# e1-tracer.net
KiCad netlist of a schematic drawn in EAGLE
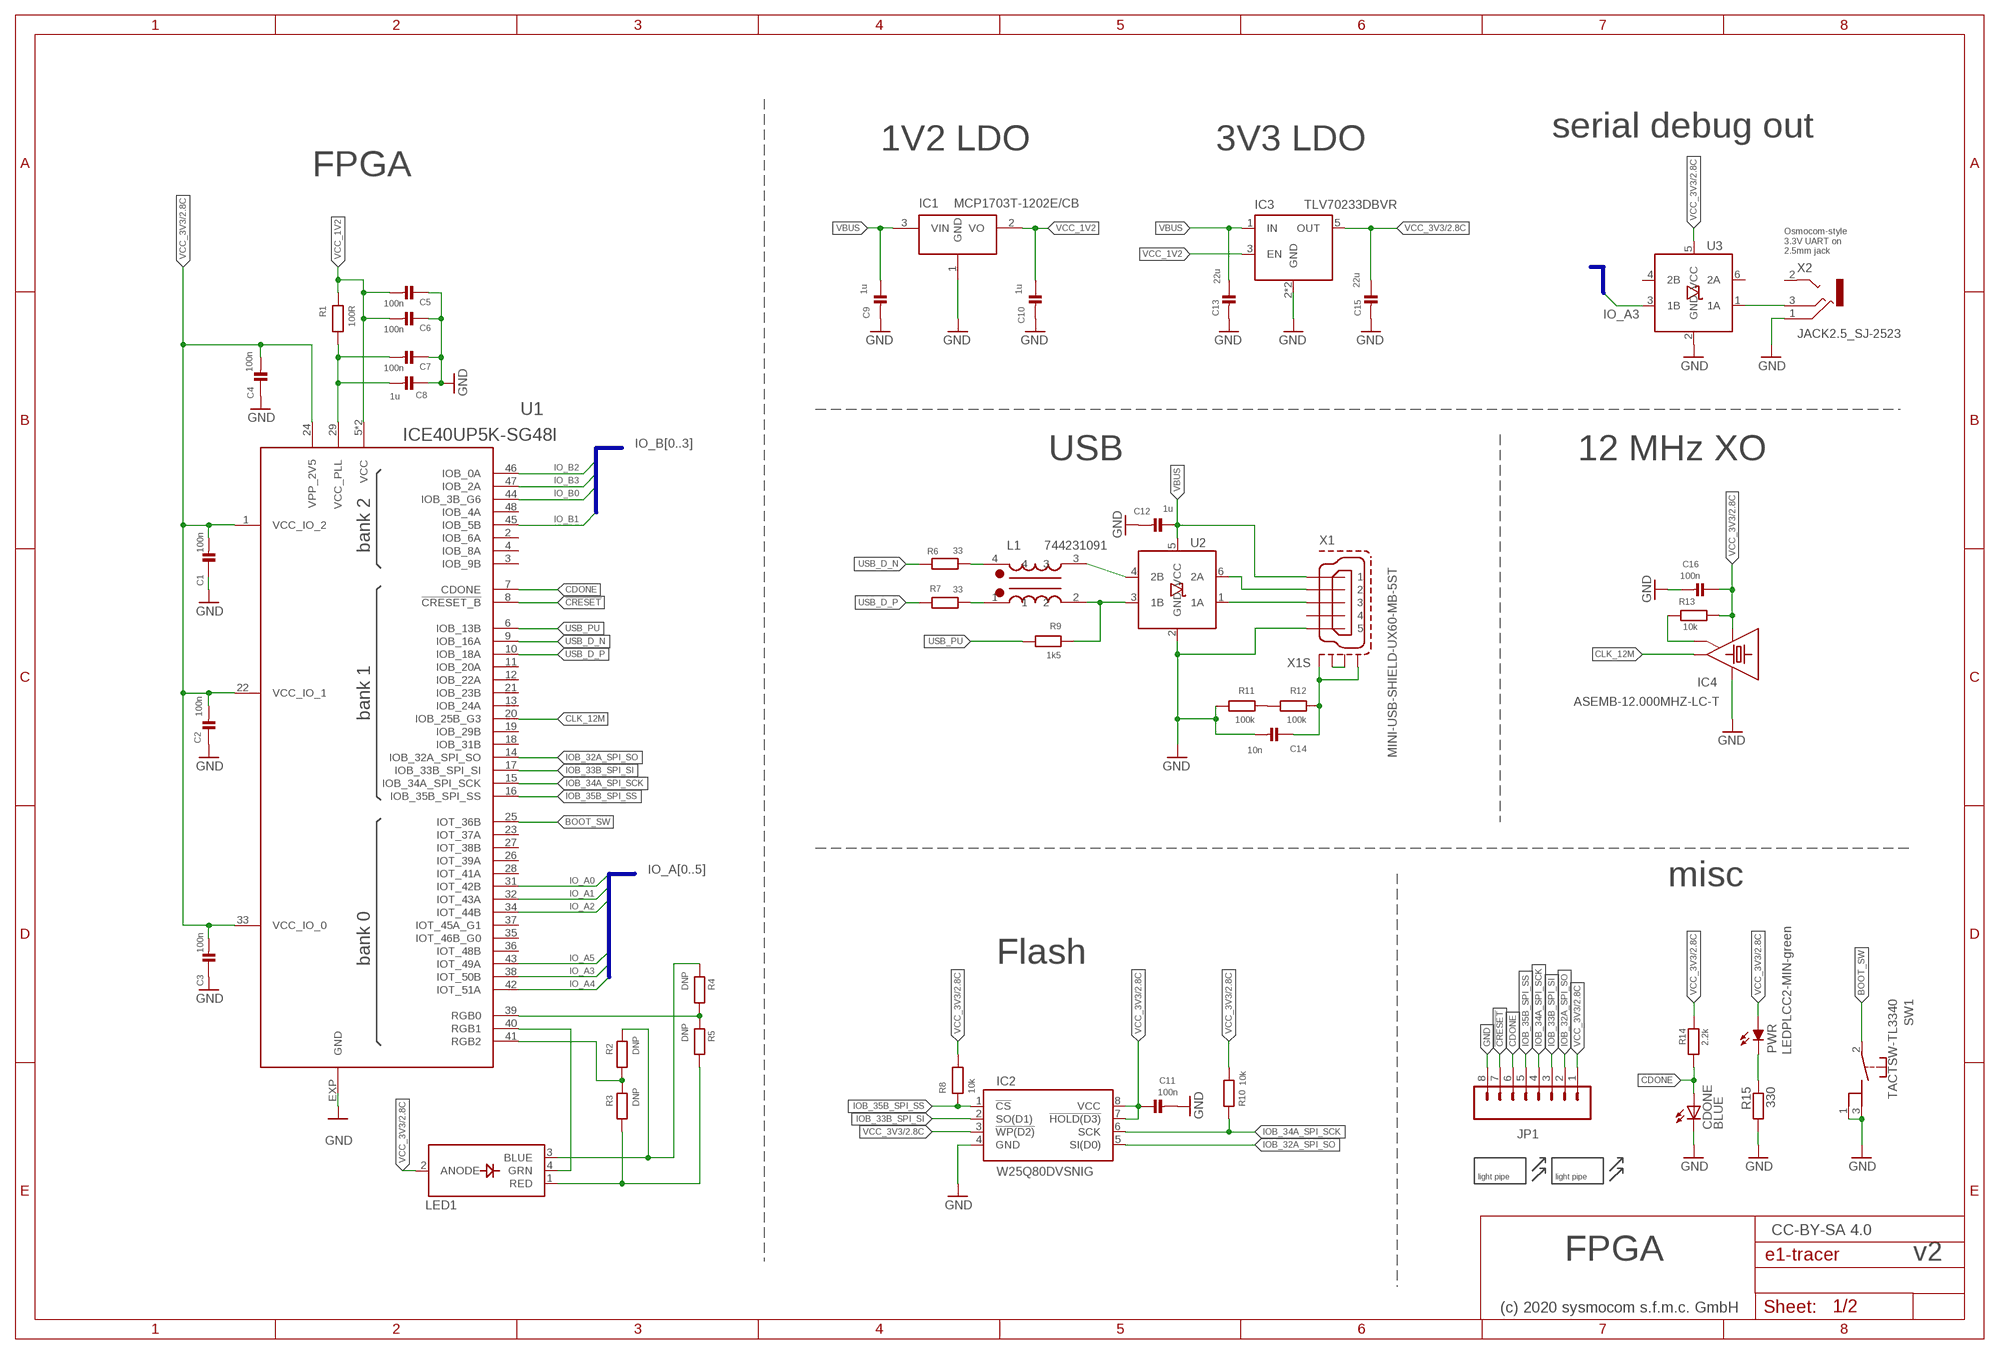
[diagram p0: schematic, sheet 1]
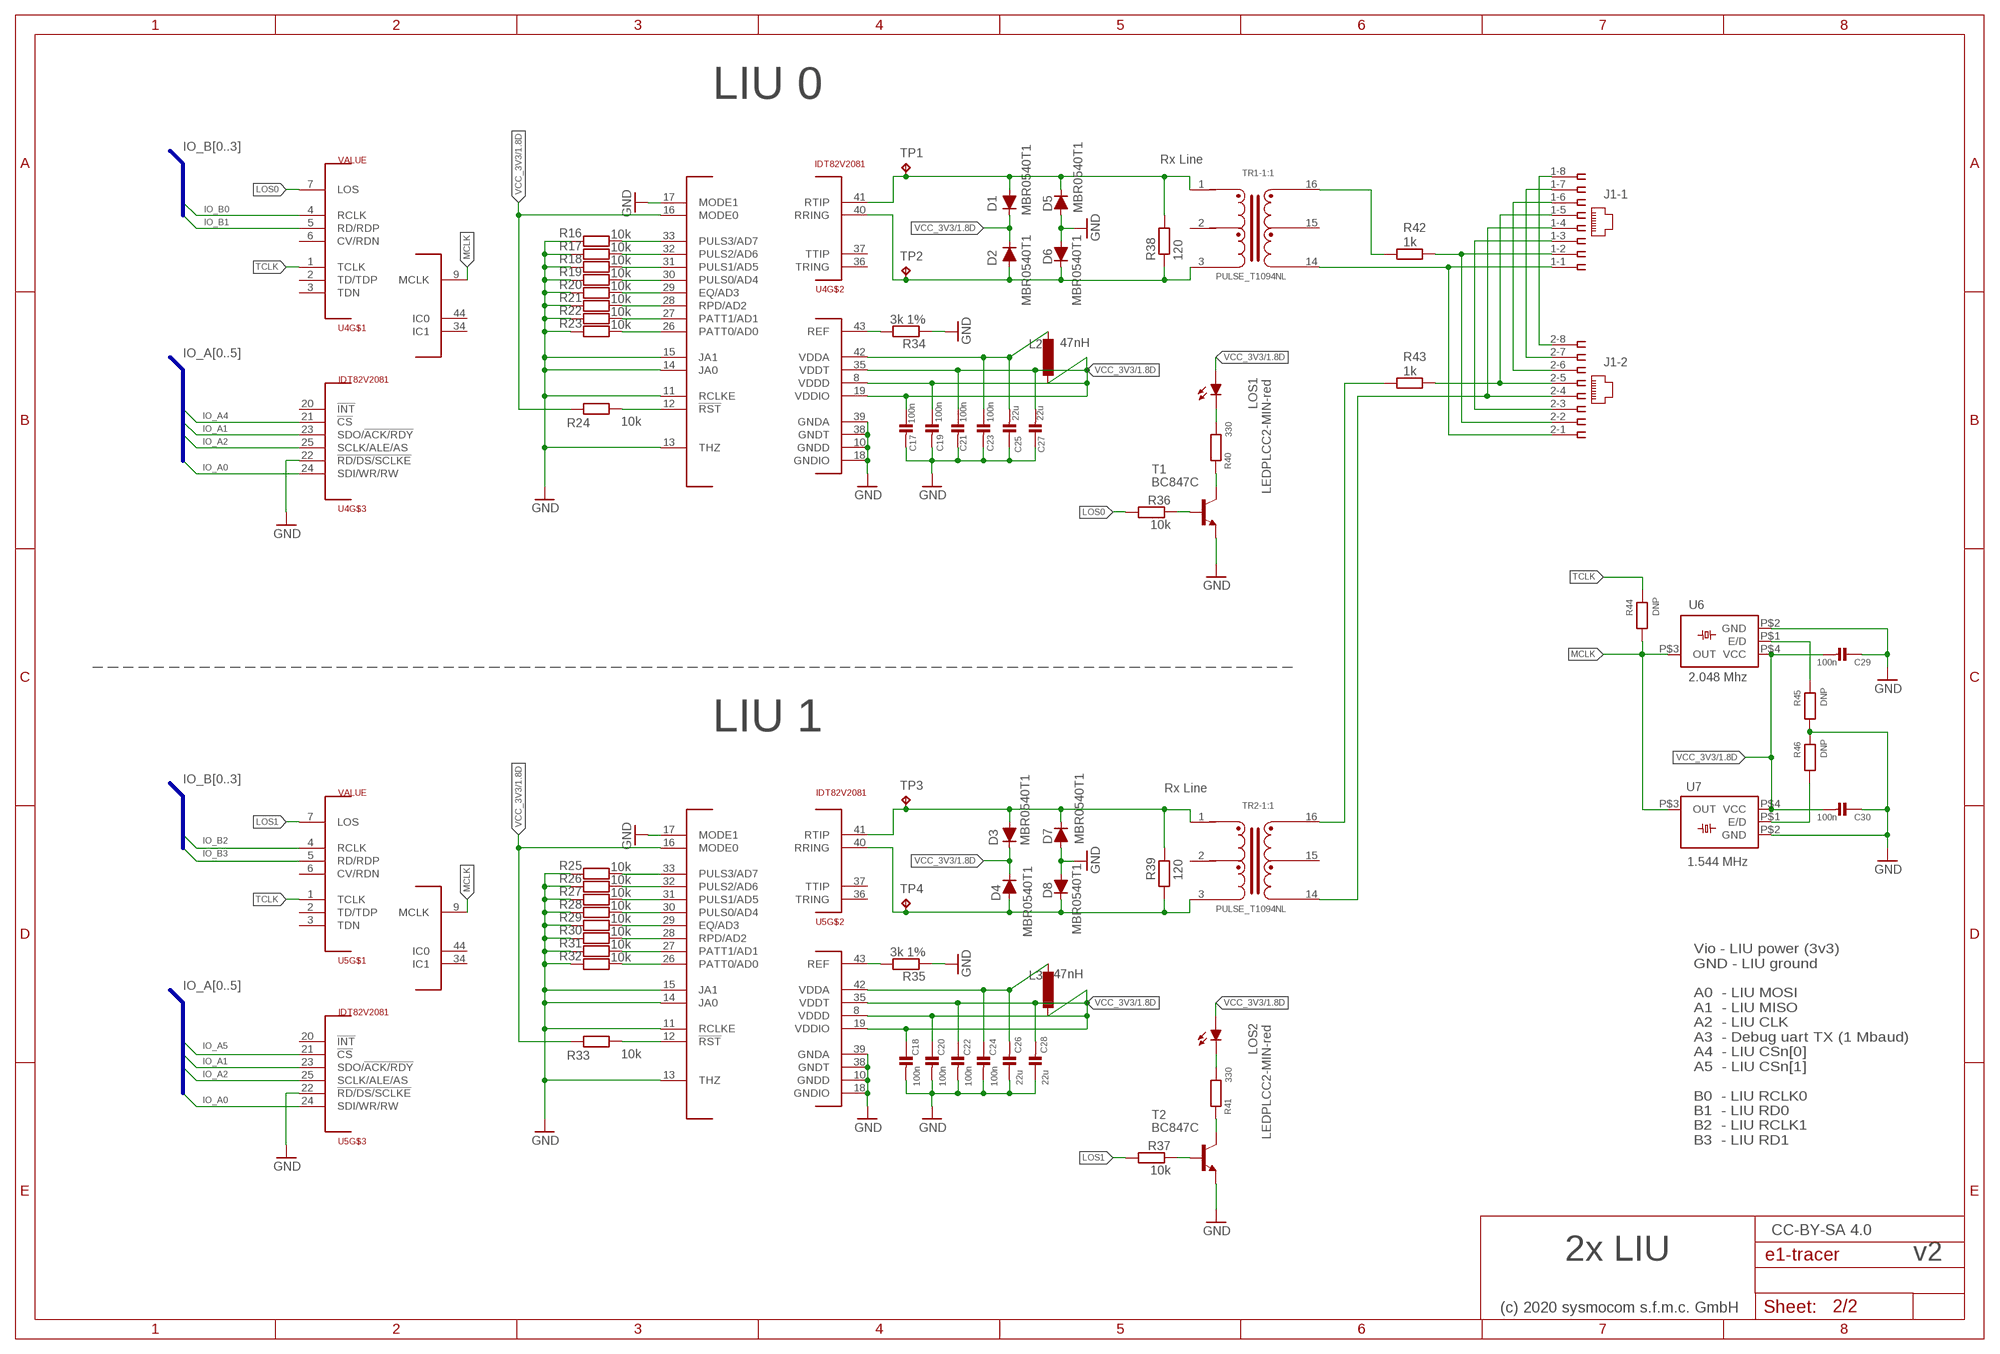
[diagram p1: schematic, sheet 2]

(export (version "E")
  (design (tool "Eeschema 10.0.6"))
  (components
    (comp (ref "C1")
      (value "100n")
      (footprint "eagle-import:_0603")
      (description "CAP CER 0.1UF 16V 10% X7R 0603")
      (fields
        (field (name "MANUFACTURER") "Samsung Electro-Mechanics America, Inc")
        (field (name "MANUFACTURERPARTNUMBER") "CL10B104KO8NNNC")
      )
      (libsource (lib "eagle-import") (part "CAP_CERAMIC_0603"))
    )
    (comp (ref "C2")
      (value "100n")
      (footprint "eagle-import:_0603")
      (description "CAP CER 0.1UF 16V 10% X7R 0603")
      (fields
        (field (name "MANUFACTURER") "Samsung Electro-Mechanics America, Inc")
        (field (name "MANUFACTURERPARTNUMBER") "CL10B104KO8NNNC")
      )
      (libsource (lib "eagle-import") (part "CAP_CERAMIC_0603"))
    )
    (comp (ref "C3")
      (value "100n")
      (footprint "eagle-import:_0603")
      (description "CAP CER 0.1UF 16V 10% X7R 0603")
      (fields
        (field (name "MANUFACTURER") "Samsung Electro-Mechanics America, Inc")
        (field (name "MANUFACTURERPARTNUMBER") "CL10B104KO8NNNC")
      )
      (libsource (lib "eagle-import") (part "CAP_CERAMIC_0603"))
    )
    (comp (ref "C4")
      (value "100n")
      (footprint "eagle-import:_0603")
      (description "CAP CER 0.1UF 16V 10% X7R 0603")
      (fields
        (field (name "MANUFACTURER") "Samsung Electro-Mechanics America, Inc")
        (field (name "MANUFACTURERPARTNUMBER") "CL10B104KO8NNNC")
      )
      (libsource (lib "eagle-import") (part "CAP_CERAMIC_0603"))
    )
    (comp (ref "C5")
      (value "100n")
      (footprint "eagle-import:_0603")
      (description "CAP CER 0.1UF 16V 10% X7R 0603")
      (fields
        (field (name "MANUFACTURER") "Samsung Electro-Mechanics America, Inc")
        (field (name "MANUFACTURERPARTNUMBER") "CL10B104KO8NNNC")
      )
      (libsource (lib "eagle-import") (part "CAP_CERAMIC_0603"))
    )
    (comp (ref "C6")
      (value "100n")
      (footprint "eagle-import:_0603")
      (description "CAP CER 0.1UF 16V 10% X7R 0603")
      (fields
        (field (name "MANUFACTURER") "Samsung Electro-Mechanics America, Inc")
        (field (name "MANUFACTURERPARTNUMBER") "CL10B104KO8NNNC")
      )
      (libsource (lib "eagle-import") (part "CAP_CERAMIC_0603"))
    )
    (comp (ref "C7")
      (value "100n")
      (footprint "eagle-import:_0603")
      (description "CAP CER 0.1UF 16V 10% X7R 0603")
      (fields
        (field (name "MANUFACTURER") "Samsung Electro-Mechanics America, Inc")
        (field (name "MANUFACTURERPARTNUMBER") "CL10B104KO8NNNC")
      )
      (libsource (lib "eagle-import") (part "CAP_CERAMIC_0603"))
    )
    (comp (ref "C8")
      (value "1u")
      (footprint "eagle-import:_0603")
      (description "CAP CER 1UF 10V X5R 0603")
      (fields
        (field (name "MANUFACTURER") "Samsung Electro-Mechanics")
        (field (name "MANUFACTURERPARTNUMBER") "CL10A105KP8NNNC")
      )
      (libsource (lib "eagle-import") (part "CAP_CERAMIC_0603"))
    )
    (comp (ref "C9")
      (value "1u")
      (footprint "eagle-import:_0603")
      (description "CAP CER 1UF 10V X5R 0603")
      (fields
        (field (name "MANUFACTURER") "Samsung Electro-Mechanics")
        (field (name "MANUFACTURERPARTNUMBER") "CL10A105KP8NNNC")
      )
      (libsource (lib "eagle-import") (part "CAP_CERAMIC_0603"))
    )
    (comp (ref "C10")
      (value "1u")
      (footprint "eagle-import:_0603")
      (description "CAP CER 1UF 10V X5R 0603")
      (fields
        (field (name "MANUFACTURER") "Samsung Electro-Mechanics")
        (field (name "MANUFACTURERPARTNUMBER") "CL10A105KP8NNNC")
      )
      (libsource (lib "eagle-import") (part "CAP_CERAMIC_0603"))
    )
    (comp (ref "C11")
      (value "100n")
      (footprint "eagle-import:_0603")
      (description "CAP CER 0.1UF 16V 10% X7R 0603")
      (fields
        (field (name "MANUFACTURER") "Samsung Electro-Mechanics America, Inc")
        (field (name "MANUFACTURERPARTNUMBER") "CL10B104KO8NNNC")
      )
      (libsource (lib "eagle-import") (part "CAP_CERAMIC_0603"))
    )
    (comp (ref "C12")
      (value "1u")
      (footprint "eagle-import:_0603")
      (description "CAP CER 1UF 10V X5R 0603")
      (fields
        (field (name "MANUFACTURER") "Samsung Electro-Mechanics")
        (field (name "MANUFACTURERPARTNUMBER") "CL10A105KP8NNNC")
      )
      (libsource (lib "eagle-import") (part "CAP_CERAMIC_0603"))
    )
    (comp (ref "C13")
      (value "22u")
      (footprint "eagle-import:1206")
      (description "CAP CER 22UF 10V 10% X5R 1206")
      (fields
        (field (name "MANUFACTURER") "Samsung Electro-Mechanics America, Inc")
        (field (name "MANUFACTURERPARTNUMBER") "CL31A226KPHNNNE")
      )
      (libsource (lib "eagle-import") (part "CAP_CERAMIC1206"))
    )
    (comp (ref "C14")
      (value "10n")
      (footprint "eagle-import:_0402")
      (description "CAP CER 10000PF 25V X7R 0402")
      (fields
        (field (name "MANUFACTURER") "Samsung Electro-Mechanics")
        (field (name "MANUFACTURERPARTNUMBER") "CL05B103KA5NNNC")
      )
      (libsource (lib "eagle-import") (part "CAP_CERAMIC_0402"))
    )
    (comp (ref "C15")
      (value "22u")
      (footprint "eagle-import:1206")
      (description "CAP CER 22UF 10V 10% X5R 1206")
      (fields
        (field (name "MANUFACTURER") "Samsung Electro-Mechanics America, Inc")
        (field (name "MANUFACTURERPARTNUMBER") "CL31A226KPHNNNE")
      )
      (libsource (lib "eagle-import") (part "CAP_CERAMIC1206"))
    )
    (comp (ref "C16")
      (value "100n")
      (footprint "eagle-import:_0603")
      (description "CAP CER 0.1UF 16V 10% X7R 0603")
      (fields
        (field (name "MANUFACTURER") "Samsung Electro-Mechanics America, Inc")
        (field (name "MANUFACTURERPARTNUMBER") "CL10B104KO8NNNC")
      )
      (libsource (lib "eagle-import") (part "CAP_CERAMIC_0603"))
    )
    (comp (ref "CDONE")
      (value "BLUE")
      (footprint "eagle-import:CHIPLED_0603")
      (description "LED BLUE CLEAR CHIP SMD")
      (fields
        (field (name "MANUFACTURER") "Lite-On Inc.")
        (field (name "MANUFACTURERPARTNUMBER") "LTST-C193TBKT-5A")
      )
      (libsource (lib "eagle-import") (part "LEDCHIPLED_0603"))
    )
    (comp (ref "IC1")
      (value "MCP1703T-1202E/CB")
      (footprint "eagle-import:SOT23-3")
      (description "IC REG LIN 1.2V 200MA SOT23A-3")
      (fields (field (name "MANUFACTURER") "Microchip Technology"))
      (libsource (lib "eagle-import") (part "MCP1700"))
    )
    (comp (ref "IC2")
      (value "W25Q80DVSNIG")
      (footprint "eagle-import:SO08COMBINED")
      (description "IC FLASH 8M SPI 104MHZ 8SOIC")
      (fields (field (name "MANUFACTURER") "Winbond Electronics"))
      (libsource (lib "eagle-import") (part "AT25SF-COMB"))
    )
    (comp (ref "IC3")
      (value "TLV70233DBVR")
      (footprint "eagle-import:SOT23-DBV")
      (description "IC REG LINEAR 3.3V 300MA SOT23-5")
      (fields (field (name "MANUFACTURER") "Texas Instruments") (field (name "OC_DIGIKEY") "296-32415-1-ND"))
      (libsource (lib "eagle-import") (part "TLV700-SOT33"))
    )
    (comp (ref "IC4")
      (value "ASEMB-12.000MHZ-LC-T")
      (footprint "eagle-import:TSX-3225")
      (description "MEMS OSC XO 12.0000MHZ CMOS SMD")
      (fields (field (name "MANUFACTURER") "Abracon LLC"))
      (libsource (lib "eagle-import") (part "ASTMLP-E-OSC"))
    )
    (comp (ref "JP1")
      (value "M08LOCK")
      (footprint "eagle-import:1X08_LOCK")
      (description "NO DESCRIPTION")
      (fields
        (field (name "MANUFACTURER") "UNKNOWN MANUFACTURER")
        (field (name "MANUFACTURERPARTNUMBER") "UNKNOWN MANUFACTURER PART NUMBER")
      )
      (libsource (lib "eagle-import") (part "M08LOCK"))
    )
    (comp (ref "L1")
      (value "744231091")
      (footprint "eagle-import:WE-CNSW_0805")
      (description "CMC 370MA 2LN 90 OHM SMD")
      (fields (field (name "MANUFACTURER") "Wurth Electronics Inc."))
      (libsource (lib "eagle-import") (part "WE-CNSW_0805"))
    )
    (comp (ref "LED1")
      (value "LED_RGB_PLCC4")
      (footprint "eagle-import:RGBLED_PLCC4")
      (description "LED RGB DIFFUSED 4PLCC SMD")
      (fields
        (field (name "MANUFACTURER") "TT Electronics/Optek Technology")
        (field (name "MANUFACTURERPARTNUMBER") "OVSARGB4R8")
      )
      (libsource (lib "eagle-import") (part "LED_RGB_PLCC4"))
    )
    (comp (ref "M1")
      (value "MENTOR_12701001")
      (footprint "eagle-import:1270.1001")
      (description "NO DESCRIPTION")
      (fields (field (name "MANUFACTURER") "Mentor") (field (name "MANUFACTURERPARTNUMBER") "1270.1001"))
      (libsource (lib "eagle-import") (part "MENTOR_12701001"))
    )
    (comp (ref "M2")
      (value "MENTOR_12701001")
      (footprint "eagle-import:1270.1001")
      (description "NO DESCRIPTION")
      (fields (field (name "MANUFACTURER") "Mentor") (field (name "MANUFACTURERPARTNUMBER") "1270.1001"))
      (libsource (lib "eagle-import") (part "MENTOR_12701001"))
    )
    (comp (ref "PWR")
      (value "LEDPLCC2-MIN-green")
      (footprint "eagle-import:PLCC2-MIN")
      (description "LED GREEN CLEAR 2PLCC SMD")
      (fields
        (field (name "MANUFACTURER") "Rohm Semiconductor")
        (field (name "MANUFACTURERPARTNUMBER") "SML-Z14PTT86A")
      )
      (libsource (lib "eagle-import") (part "LEDPLCC2-MIN"))
    )
    (comp (ref "R1")
      (value "100R")
      (footprint "eagle-import:_0603")
      (description "RES 100 OHM 5%% 1/10W 0603")
      (fields
        (field (name "MANUFACTURER") "Stackpole Electronics Inc")
        (field (name "MANUFACTURERPARTNUMBER") "RMCF0603JT100R")
      )
      (libsource (lib "eagle-import") (part "RESISTOR_0603"))
    )
    (comp (ref "R2")
      (value "DNP")
      (footprint "eagle-import:_0603")
      (description "RES SMD 0 OHM JUMPER 1/10W 0603")
      (fields
        (field (name "MANUFACTURER") "Panasonic Electronic Components")
        (field (name "MANUFACTURERPARTNUMBER") "ERJ-3GEY0R00V")
      )
      (libsource (lib "eagle-import") (part "RESISTOR_0603"))
    )
    (comp (ref "R3")
      (value "DNP")
      (footprint "eagle-import:_0603")
      (description "RES SMD 0 OHM JUMPER 1/10W 0603")
      (fields
        (field (name "MANUFACTURER") "Panasonic Electronic Components")
        (field (name "MANUFACTURERPARTNUMBER") "ERJ-3GEY0R00V")
      )
      (libsource (lib "eagle-import") (part "RESISTOR_0603"))
    )
    (comp (ref "R4")
      (value "DNP")
      (footprint "eagle-import:_0603")
      (description "RES SMD 0 OHM JUMPER 1/10W 0603")
      (fields
        (field (name "MANUFACTURER") "Panasonic Electronic Components")
        (field (name "MANUFACTURERPARTNUMBER") "ERJ-3GEY0R00V")
      )
      (libsource (lib "eagle-import") (part "RESISTOR_0603"))
    )
    (comp (ref "R5")
      (value "DNP")
      (footprint "eagle-import:_0603")
      (description "RES SMD 0 OHM JUMPER 1/10W 0603")
      (fields
        (field (name "MANUFACTURER") "Panasonic Electronic Components")
        (field (name "MANUFACTURERPARTNUMBER") "ERJ-3GEY0R00V")
      )
      (libsource (lib "eagle-import") (part "RESISTOR_0603"))
    )
    (comp (ref "R6")
      (value "33")
      (footprint "eagle-import:_0402")
      (description "RES SMD 33 OHM 1%% 1/16W 0402")
      (fields (field (name "MANUFACTURER") "Yageo") (field (name "MANUFACTURERPARTNUMBER") "RC0402FR-0733RL"))
      (libsource (lib "eagle-import") (part "RESISTOR_0402"))
    )
    (comp (ref "R7")
      (value "33")
      (footprint "eagle-import:_0402")
      (description "RES SMD 33 OHM 1%% 1/16W 0402")
      (fields (field (name "MANUFACTURER") "Yageo") (field (name "MANUFACTURERPARTNUMBER") "RC0402FR-0733RL"))
      (libsource (lib "eagle-import") (part "RESISTOR_0402"))
    )
    (comp (ref "R8")
      (value "10k")
      (footprint "eagle-import:_0603")
      (description "RES 10K OHM 5%% 1/10W 0603")
      (fields
        (field (name "MANUFACTURER") "Stackpole Electronics Inc")
        (field (name "MANUFACTURERPARTNUMBER") "RMCF0603JT10K0")
      )
      (libsource (lib "eagle-import") (part "RESISTOR_0603"))
    )
    (comp (ref "R9")
      (value "1k5")
      (footprint "eagle-import:_0603")
      (description "RES 1.5K OHM 5%% 1/10W 0603")
      (fields
        (field (name "MANUFACTURER") "Stackpole Electronics Inc")
        (field (name "MANUFACTURERPARTNUMBER") "RMCF0603JT1K50")
      )
      (libsource (lib "eagle-import") (part "RESISTOR_0603"))
    )
    (comp (ref "R10")
      (value "10k")
      (footprint "eagle-import:_0603")
      (description "RES 10K OHM 5%% 1/10W 0603")
      (fields
        (field (name "MANUFACTURER") "Stackpole Electronics Inc")
        (field (name "MANUFACTURERPARTNUMBER") "RMCF0603JT10K0")
      )
      (libsource (lib "eagle-import") (part "RESISTOR_0603"))
    )
    (comp (ref "R11")
      (value "100k")
      (footprint "eagle-import:_0603")
      (description "RES SMD 100K OHM 5%% 1/10W 0603")
      (fields
        (field (name "MANUFACTURER") "Yageo")
        (field (name "MANUFACTURERPARTNUMBER") "RC0603JR-07100KL")
      )
      (libsource (lib "eagle-import") (part "RESISTOR_0603"))
    )
    (comp (ref "R12")
      (value "100k")
      (footprint "eagle-import:_0603")
      (description "RES SMD 100K OHM 5%% 1/10W 0603")
      (fields
        (field (name "MANUFACTURER") "Yageo")
        (field (name "MANUFACTURERPARTNUMBER") "RC0603JR-07100KL")
      )
      (libsource (lib "eagle-import") (part "RESISTOR_0603"))
    )
    (comp (ref "R13")
      (value "10k")
      (footprint "eagle-import:_0603")
      (description "RES 10K OHM 5%% 1/10W 0603")
      (fields
        (field (name "MANUFACTURER") "Stackpole Electronics Inc")
        (field (name "MANUFACTURERPARTNUMBER") "RMCF0603JT10K0")
      )
      (libsource (lib "eagle-import") (part "RESISTOR_0603"))
    )
    (comp (ref "R14")
      (value "2.2k")
      (footprint "eagle-import:_0603")
      (description "RES 2.2K OHM 5%% 1/10W 0603")
      (fields
        (field (name "MANUFACTURER") "Stackpole Electronics Inc")
        (field (name "MANUFACTURERPARTNUMBER") "RMCF0603JT2K20")
      )
      (libsource (lib "eagle-import") (part "RESISTOR_0603"))
    )
    (comp (ref "R15")
      (value "330")
      (footprint "eagle-import:_0603")
      (description "RES SMD 330 OHM 1%% 1/10W 0603")
      (fields
        (field (name "MANUFACTURER") "Yageo")
        (field (name "MANUFACTURERPARTNUMBER") "RC0603FR-07330RL")
      )
      (libsource (lib "eagle-import") (part "RESISTOR_0603"))
    )
    (comp (ref "SW1")
      (value "TACTSW-TL3340")
      (footprint "eagle-import:TL3340-ORIG")
      (description "SWITCH TACTILE SPST-NO 0.05A 12V")
      (fields
        (field (name "MANUFACTURER") "E-Switch")
        (field (name "MANUFACTURERPARTNUMBER") "TL3340AF160QG")
      )
      (libsource (lib "eagle-import") (part "TL3340"))
    )
    (comp (ref "U1")
      (value "ICE40UP5K-SG48I")
      (footprint "eagle-import:QFN48")
      (description "IC FPGA 39 I/O 48QFN")
      (fields (field (name "MANUFACTURER") "Lattice Semiconductor Corporation"))
      (libsource (lib "eagle-import") (part "ICE40UP5K-SG48I"))
    )
    (comp (ref "U2")
      (value "IP4234CZ6")
      (footprint "eagle-import:TSOP-6")
      (description "TVS DIODE 5.5V 6TSOP")
      (fields
        (field (name "MANUFACTURER") "Nexperia USA Inc.")
        (field (name "MANUFACTURERPARTNUMBER") "IP4234CZ6,125")
      )
      (libsource (lib "eagle-import") (part "IP4234CZ6"))
    )
    (comp (ref "U3")
      (value "IP4234CZ6")
      (footprint "eagle-import:TSOP-6")
      (description "TVS DIODE 5.5V 6TSOP")
      (fields
        (field (name "MANUFACTURER") "Nexperia USA Inc.")
        (field (name "MANUFACTURERPARTNUMBER") "IP4234CZ6,125")
      )
      (libsource (lib "eagle-import") (part "IP4234CZ6"))
    )
    (comp (ref "X1")
      (value "MINI-USB-SHIELD-UX60-MB-5ST")
      (footprint "eagle-import:UX60-MB-5ST")
      (description "CONN RCPT USB2.0 MINI B SMD R/A")
      (fields
        (field (name "MANUFACTURER") "Hirose Electric Co Ltd")
        (field (name "MANUFACTURERPARTNUMBER") "UX60A-MB-5ST")
        (field (name "CLASS") "CONNECTOR")
        (field (name "LINK") "https://www.digikey.de/product-detail/de/hirose-electric-co-ltd/UX60A-MB-5ST/H2961CT-ND/597540")
        (field (name "POPULATED") "TRUE")
        (field (name "ROHSCERTIFICATE") "Bleifrei / RoHS-konform")
        (field (name "SOURCE") "DIGIKEY")
        (field (name "SOURCEPARTNUMBER") "H2961CT-ND")
      )
      (libsource (lib "eagle-import") (part "MINI-USB-SHIELD-UX60-MB-5ST"))
    )
    (comp (ref "X2")
      (value "JACK2.5_SJ-2523")
      (footprint "eagle-import:JACK2.5_SJ-2523")
      (description "CONN JACK STEREO 2.5MM SMD R/A")
      (fields
        (field (name "MANUFACTURER") "CUI Inc.")
        (field (name "MANUFACTURERPARTNUMBER") "SJ-2523-SMT-TR")
      )
      (libsource (lib "eagle-import") (part "JACK2.5_SJ-2523"))
    )
    (comp (ref "C17")
      (value "100n")
      (footprint "eagle-import:_0603")
      (description "CAP CER 0.1UF 16V 10% X7R 0603")
      (fields
        (field (name "MANUFACTURER") "Samsung Electro-Mechanics America, Inc")
        (field (name "MANUFACTURERPARTNUMBER") "CL10B104KO8NNNC")
      )
      (libsource (lib "eagle-import") (part "CAP_CERAMIC_0603"))
    )
    (comp (ref "C18")
      (value "100n")
      (footprint "eagle-import:_0603")
      (description "CAP CER 0.1UF 16V 10% X7R 0603")
      (fields
        (field (name "MANUFACTURER") "Samsung Electro-Mechanics America, Inc")
        (field (name "MANUFACTURERPARTNUMBER") "CL10B104KO8NNNC")
      )
      (libsource (lib "eagle-import") (part "CAP_CERAMIC_0603"))
    )
    (comp (ref "C19")
      (value "100n")
      (footprint "eagle-import:_0603")
      (description "CAP CER 0.1UF 16V 10% X7R 0603")
      (fields
        (field (name "MANUFACTURER") "Samsung Electro-Mechanics America, Inc")
        (field (name "MANUFACTURERPARTNUMBER") "CL10B104KO8NNNC")
      )
      (libsource (lib "eagle-import") (part "CAP_CERAMIC_0603"))
    )
    (comp (ref "C20")
      (value "100n")
      (footprint "eagle-import:_0603")
      (description "CAP CER 0.1UF 16V 10% X7R 0603")
      (fields
        (field (name "MANUFACTURER") "Samsung Electro-Mechanics America, Inc")
        (field (name "MANUFACTURERPARTNUMBER") "CL10B104KO8NNNC")
      )
      (libsource (lib "eagle-import") (part "CAP_CERAMIC_0603"))
    )
    (comp (ref "C21")
      (value "100n")
      (footprint "eagle-import:_0603")
      (description "CAP CER 0.1UF 16V 10% X7R 0603")
      (fields
        (field (name "MANUFACTURER") "Samsung Electro-Mechanics America, Inc")
        (field (name "MANUFACTURERPARTNUMBER") "CL10B104KO8NNNC")
      )
      (libsource (lib "eagle-import") (part "CAP_CERAMIC_0603"))
    )
    (comp (ref "C22")
      (value "100n")
      (footprint "eagle-import:_0603")
      (description "CAP CER 0.1UF 16V 10% X7R 0603")
      (fields
        (field (name "MANUFACTURER") "Samsung Electro-Mechanics America, Inc")
        (field (name "MANUFACTURERPARTNUMBER") "CL10B104KO8NNNC")
      )
      (libsource (lib "eagle-import") (part "CAP_CERAMIC_0603"))
    )
    (comp (ref "C23")
      (value "100n")
      (footprint "eagle-import:_0603")
      (description "CAP CER 0.1UF 16V 10% X7R 0603")
      (fields
        (field (name "MANUFACTURER") "Samsung Electro-Mechanics America, Inc")
        (field (name "MANUFACTURERPARTNUMBER") "CL10B104KO8NNNC")
      )
      (libsource (lib "eagle-import") (part "CAP_CERAMIC_0603"))
    )
    (comp (ref "C24")
      (value "100n")
      (footprint "eagle-import:_0603")
      (description "CAP CER 0.1UF 16V 10% X7R 0603")
      (fields
        (field (name "MANUFACTURER") "Samsung Electro-Mechanics America, Inc")
        (field (name "MANUFACTURERPARTNUMBER") "CL10B104KO8NNNC")
      )
      (libsource (lib "eagle-import") (part "CAP_CERAMIC_0603"))
    )
    (comp (ref "C25")
      (value "22u")
      (footprint "eagle-import:_0805")
      (description "CAP CER 22UF 6.3V X5R 0805")
      (fields
        (field (name "MANUFACTURER") "KEMET")
        (field (name "MANUFACTURERPARTNUMBER") "C0805C226M9PACTU")
      )
      (libsource (lib "eagle-import") (part "CAP_CERAMIC_0805"))
    )
    (comp (ref "C26")
      (value "22u")
      (footprint "eagle-import:_0805")
      (description "CAP CER 22UF 6.3V X5R 0805")
      (fields
        (field (name "MANUFACTURER") "KEMET")
        (field (name "MANUFACTURERPARTNUMBER") "C0805C226M9PACTU")
      )
      (libsource (lib "eagle-import") (part "CAP_CERAMIC_0805"))
    )
    (comp (ref "C27")
      (value "22u")
      (footprint "eagle-import:_0805")
      (description "CAP CER 22UF 6.3V X5R 0805")
      (fields
        (field (name "MANUFACTURER") "KEMET")
        (field (name "MANUFACTURERPARTNUMBER") "C0805C226M9PACTU")
      )
      (libsource (lib "eagle-import") (part "CAP_CERAMIC_0805"))
    )
    (comp (ref "C28")
      (value "22u")
      (footprint "eagle-import:_0805")
      (description "CAP CER 22UF 6.3V X5R 0805")
      (fields
        (field (name "MANUFACTURER") "KEMET")
        (field (name "MANUFACTURERPARTNUMBER") "C0805C226M9PACTU")
      )
      (libsource (lib "eagle-import") (part "CAP_CERAMIC_0805"))
    )
    (comp (ref "C29")
      (value "100n")
      (footprint "eagle-import:_0603")
      (description "CAP CER 0.1UF 16V 10% X7R 0603")
      (fields
        (field (name "MANUFACTURER") "Samsung Electro-Mechanics America, Inc")
        (field (name "MANUFACTURERPARTNUMBER") "CL10B104KO8NNNC")
      )
      (libsource (lib "eagle-import") (part "CAP_CERAMIC_0603"))
    )
    (comp (ref "C30")
      (value "100n")
      (footprint "eagle-import:_0603")
      (description "CAP CER 0.1UF 16V 10% X7R 0603")
      (fields
        (field (name "MANUFACTURER") "Samsung Electro-Mechanics America, Inc")
        (field (name "MANUFACTURERPARTNUMBER") "CL10B104KO8NNNC")
      )
      (libsource (lib "eagle-import") (part "CAP_CERAMIC_0603"))
    )
    (comp (ref "D1")
      (value "MBR0540T1")
      (footprint "eagle-import:SOD123")
      (description "DIODE SCHOTTKY 40V 500MA SOD123")
      (fields
        (field (name "MANUFACTURER") "ON Semiconductor")
        (field (name "MANUFACTURERPARTNUMBER") "MBR0540T1G")
      )
      (libsource (lib "eagle-import") (part "D-FILL-SOD123"))
    )
    (comp (ref "D2")
      (value "MBR0540T1")
      (footprint "eagle-import:SOD123")
      (description "DIODE SCHOTTKY 40V 500MA SOD123")
      (fields
        (field (name "MANUFACTURER") "ON Semiconductor")
        (field (name "MANUFACTURERPARTNUMBER") "MBR0540T1G")
      )
      (libsource (lib "eagle-import") (part "D-FILL-SOD123"))
    )
    (comp (ref "D3")
      (value "MBR0540T1")
      (footprint "eagle-import:SOD123")
      (description "DIODE SCHOTTKY 40V 500MA SOD123")
      (fields
        (field (name "MANUFACTURER") "ON Semiconductor")
        (field (name "MANUFACTURERPARTNUMBER") "MBR0540T1G")
      )
      (libsource (lib "eagle-import") (part "D-FILL-SOD123"))
    )
    (comp (ref "D4")
      (value "MBR0540T1")
      (footprint "eagle-import:SOD123")
      (description "DIODE SCHOTTKY 40V 500MA SOD123")
      (fields
        (field (name "MANUFACTURER") "ON Semiconductor")
        (field (name "MANUFACTURERPARTNUMBER") "MBR0540T1G")
      )
      (libsource (lib "eagle-import") (part "D-FILL-SOD123"))
    )
    (comp (ref "D5")
      (value "MBR0540T1")
      (footprint "eagle-import:SOD123")
      (description "DIODE SCHOTTKY 40V 500MA SOD123")
      (fields
        (field (name "MANUFACTURER") "ON Semiconductor")
        (field (name "MANUFACTURERPARTNUMBER") "MBR0540T1G")
      )
      (libsource (lib "eagle-import") (part "D-FILL-SOD123"))
    )
    (comp (ref "D6")
      (value "MBR0540T1")
      (footprint "eagle-import:SOD123")
      (description "DIODE SCHOTTKY 40V 500MA SOD123")
      (fields
        (field (name "MANUFACTURER") "ON Semiconductor")
        (field (name "MANUFACTURERPARTNUMBER") "MBR0540T1G")
      )
      (libsource (lib "eagle-import") (part "D-FILL-SOD123"))
    )
    (comp (ref "D7")
      (value "MBR0540T1")
      (footprint "eagle-import:SOD123")
      (description "DIODE SCHOTTKY 40V 500MA SOD123")
      (fields
        (field (name "MANUFACTURER") "ON Semiconductor")
        (field (name "MANUFACTURERPARTNUMBER") "MBR0540T1G")
      )
      (libsource (lib "eagle-import") (part "D-FILL-SOD123"))
    )
    (comp (ref "D8")
      (value "MBR0540T1")
      (footprint "eagle-import:SOD123")
      (description "DIODE SCHOTTKY 40V 500MA SOD123")
      (fields
        (field (name "MANUFACTURER") "ON Semiconductor")
        (field (name "MANUFACTURERPARTNUMBER") "MBR0540T1G")
      )
      (libsource (lib "eagle-import") (part "D-FILL-SOD123"))
    )
    (comp (ref "J1")
      (value "PASSTHROUGH")
      (footprint "eagle-import:557560-1")
      (description "CONN MOD JACK 8P8C R/A UNSHLD")
      (fields
        (field (name "CLASS") "CONNECTOR\\JUMPER")
        (field (name "LINK") "https://www.digikey.de/product-detail/de/te-connectivity-amp-connectors/5557560-1/A31449-ND")
        (field (name "MANUFACTURER") "TE Connectivity AMP Connectors")
        (field (name "MANUFACTURERPARTNUMBER") "5557560-1")
        (field (name "POPULATED") "TRUE")
        (field (name "ROHSCERTIFICATE") "RoHS-konform")
        (field (name "SOURCE") "DIGIKEY")
        (field (name "SOURCEPARTNUMBER") "A31449-ND")
      )
      (libsource (lib "eagle-import") (part "557560-1"))
    )
    (comp (ref "L2")
      (value "47nH")
      (footprint "eagle-import:0805")
      (description "FIXED IND 47NH 300MA 700MOHM SMD")
      (fields
        (field (name "MANUFACTURER") "Bourns Inc.")
        (field (name "MANUFACTURERPARTNUMBER") "CE201210-47NJ")
      )
      (libsource (lib "eagle-import") (part "INDUCTOR0805"))
    )
    (comp (ref "L3")
      (value "47nH")
      (footprint "eagle-import:0805")
      (description "FIXED IND 47NH 300MA 700MOHM SMD")
      (fields
        (field (name "MANUFACTURER") "Bourns Inc.")
        (field (name "MANUFACTURERPARTNUMBER") "CE201210-47NJ")
      )
      (libsource (lib "eagle-import") (part "INDUCTOR0805"))
    )
    (comp (ref "LOS1")
      (value "LEDPLCC2-MIN-red")
      (footprint "eagle-import:PLCC2-MIN")
      (description "LED RED CLEAR 2PLCC SMD")
      (fields
        (field (name "MANUFACTURER") "OSRAM Opto Semiconductors Inc.")
        (field (name "MANUFACTURERPARTNUMBER") "LS T676-R1S1-1-Z")
      )
      (libsource (lib "eagle-import") (part "LEDPLCC2-MIN"))
    )
    (comp (ref "LOS2")
      (value "LEDPLCC2-MIN-red")
      (footprint "eagle-import:PLCC2-MIN")
      (description "LED RED CLEAR 2PLCC SMD")
      (fields
        (field (name "MANUFACTURER") "OSRAM Opto Semiconductors Inc.")
        (field (name "MANUFACTURERPARTNUMBER") "LS T676-R1S1-1-Z")
      )
      (libsource (lib "eagle-import") (part "LEDPLCC2-MIN"))
    )
    (comp (ref "R16")
      (value "10k")
      (footprint "eagle-import:_0603")
      (description "RES 10K OHM 5%% 1/10W 0603")
      (fields
        (field (name "MANUFACTURER") "Stackpole Electronics Inc")
        (field (name "MANUFACTURERPARTNUMBER") "RMCF0603JT10K0")
      )
      (libsource (lib "eagle-import") (part "RESISTOR_0603"))
    )
    (comp (ref "R17")
      (value "10k")
      (footprint "eagle-import:_0603")
      (description "RES 10K OHM 5%% 1/10W 0603")
      (fields
        (field (name "MANUFACTURER") "Stackpole Electronics Inc")
        (field (name "MANUFACTURERPARTNUMBER") "RMCF0603JT10K0")
      )
      (libsource (lib "eagle-import") (part "RESISTOR_0603"))
    )
    (comp (ref "R18")
      (value "10k")
      (footprint "eagle-import:_0603")
      (description "RES 10K OHM 5%% 1/10W 0603")
      (fields
        (field (name "MANUFACTURER") "Stackpole Electronics Inc")
        (field (name "MANUFACTURERPARTNUMBER") "RMCF0603JT10K0")
      )
      (libsource (lib "eagle-import") (part "RESISTOR_0603"))
    )
    (comp (ref "R19")
      (value "10k")
      (footprint "eagle-import:_0603")
      (description "RES 10K OHM 5%% 1/10W 0603")
      (fields
        (field (name "MANUFACTURER") "Stackpole Electronics Inc")
        (field (name "MANUFACTURERPARTNUMBER") "RMCF0603JT10K0")
      )
      (libsource (lib "eagle-import") (part "RESISTOR_0603"))
    )
    (comp (ref "R20")
      (value "10k")
      (footprint "eagle-import:_0603")
      (description "RES 10K OHM 5%% 1/10W 0603")
      (fields
        (field (name "MANUFACTURER") "Stackpole Electronics Inc")
        (field (name "MANUFACTURERPARTNUMBER") "RMCF0603JT10K0")
      )
      (libsource (lib "eagle-import") (part "RESISTOR_0603"))
    )
    (comp (ref "R21")
      (value "10k")
      (footprint "eagle-import:_0603")
      (description "RES 10K OHM 5%% 1/10W 0603")
      (fields
        (field (name "MANUFACTURER") "Stackpole Electronics Inc")
        (field (name "MANUFACTURERPARTNUMBER") "RMCF0603JT10K0")
      )
      (libsource (lib "eagle-import") (part "RESISTOR_0603"))
    )
    (comp (ref "R22")
      (value "10k")
      (footprint "eagle-import:_0603")
      (description "RES 10K OHM 5%% 1/10W 0603")
      (fields
        (field (name "MANUFACTURER") "Stackpole Electronics Inc")
        (field (name "MANUFACTURERPARTNUMBER") "RMCF0603JT10K0")
      )
      (libsource (lib "eagle-import") (part "RESISTOR_0603"))
    )
    (comp (ref "R23")
      (value "10k")
      (footprint "eagle-import:_0603")
      (description "RES 10K OHM 5%% 1/10W 0603")
      (fields
        (field (name "MANUFACTURER") "Stackpole Electronics Inc")
        (field (name "MANUFACTURERPARTNUMBER") "RMCF0603JT10K0")
      )
      (libsource (lib "eagle-import") (part "RESISTOR_0603"))
    )
    (comp (ref "R24")
      (value "10k")
      (footprint "eagle-import:_0603")
      (description "RES 10K OHM 5%% 1/10W 0603")
      (fields
        (field (name "MANUFACTURER") "Stackpole Electronics Inc")
        (field (name "MANUFACTURERPARTNUMBER") "RMCF0603JT10K0")
      )
      (libsource (lib "eagle-import") (part "RESISTOR_0603"))
    )
    (comp (ref "R25")
      (value "10k")
      (footprint "eagle-import:_0603")
      (description "RES 10K OHM 5%% 1/10W 0603")
      (fields
        (field (name "MANUFACTURER") "Stackpole Electronics Inc")
        (field (name "MANUFACTURERPARTNUMBER") "RMCF0603JT10K0")
      )
      (libsource (lib "eagle-import") (part "RESISTOR_0603"))
    )
    (comp (ref "R26")
      (value "10k")
      (footprint "eagle-import:_0603")
      (description "RES 10K OHM 5%% 1/10W 0603")
      (fields
        (field (name "MANUFACTURER") "Stackpole Electronics Inc")
        (field (name "MANUFACTURERPARTNUMBER") "RMCF0603JT10K0")
      )
      (libsource (lib "eagle-import") (part "RESISTOR_0603"))
    )
    (comp (ref "R27")
      (value "10k")
      (footprint "eagle-import:_0603")
      (description "RES 10K OHM 5%% 1/10W 0603")
      (fields
        (field (name "MANUFACTURER") "Stackpole Electronics Inc")
        (field (name "MANUFACTURERPARTNUMBER") "RMCF0603JT10K0")
      )
      (libsource (lib "eagle-import") (part "RESISTOR_0603"))
    )
    (comp (ref "R28")
      (value "10k")
      (footprint "eagle-import:_0603")
      (description "RES 10K OHM 5%% 1/10W 0603")
      (fields
        (field (name "MANUFACTURER") "Stackpole Electronics Inc")
        (field (name "MANUFACTURERPARTNUMBER") "RMCF0603JT10K0")
      )
      (libsource (lib "eagle-import") (part "RESISTOR_0603"))
    )
    (comp (ref "R29")
      (value "10k")
      (footprint "eagle-import:_0603")
      (description "RES 10K OHM 5%% 1/10W 0603")
      (fields
        (field (name "MANUFACTURER") "Stackpole Electronics Inc")
        (field (name "MANUFACTURERPARTNUMBER") "RMCF0603JT10K0")
      )
      (libsource (lib "eagle-import") (part "RESISTOR_0603"))
    )
    (comp (ref "R30")
      (value "10k")
      (footprint "eagle-import:_0603")
      (description "RES 10K OHM 5%% 1/10W 0603")
      (fields
        (field (name "MANUFACTURER") "Stackpole Electronics Inc")
        (field (name "MANUFACTURERPARTNUMBER") "RMCF0603JT10K0")
      )
      (libsource (lib "eagle-import") (part "RESISTOR_0603"))
    )
    (comp (ref "R31")
      (value "10k")
      (footprint "eagle-import:_0603")
      (description "RES 10K OHM 5%% 1/10W 0603")
      (fields
        (field (name "MANUFACTURER") "Stackpole Electronics Inc")
        (field (name "MANUFACTURERPARTNUMBER") "RMCF0603JT10K0")
      )
      (libsource (lib "eagle-import") (part "RESISTOR_0603"))
    )
    (comp (ref "R32")
      (value "10k")
      (footprint "eagle-import:_0603")
      (description "RES 10K OHM 5%% 1/10W 0603")
      (fields
        (field (name "MANUFACTURER") "Stackpole Electronics Inc")
        (field (name "MANUFACTURERPARTNUMBER") "RMCF0603JT10K0")
      )
      (libsource (lib "eagle-import") (part "RESISTOR_0603"))
    )
    (comp (ref "R33")
      (value "10k")
      (footprint "eagle-import:_0603")
      (description "RES 10K OHM 5%% 1/10W 0603")
      (fields
        (field (name "MANUFACTURER") "Stackpole Electronics Inc")
        (field (name "MANUFACTURERPARTNUMBER") "RMCF0603JT10K0")
      )
      (libsource (lib "eagle-import") (part "RESISTOR_0603"))
    )
    (comp (ref "R34")
      (value "3k 1%")
      (footprint "eagle-import:_0603")
      (description "RES 3K OHM 1%% 1/10W 0603")
      (fields
        (field (name "MANUFACTURER") "Stackpole Electronics Inc")
        (field (name "MANUFACTURERPARTNUMBER") "RMCF0603FT3K00")
      )
      (libsource (lib "eagle-import") (part "RESISTOR_0603"))
    )
    (comp (ref "R35")
      (value "3k 1%")
      (footprint "eagle-import:_0603")
      (description "RES 3K OHM 1%% 1/10W 0603")
      (fields
        (field (name "MANUFACTURER") "Stackpole Electronics Inc")
        (field (name "MANUFACTURERPARTNUMBER") "RMCF0603FT3K00")
      )
      (libsource (lib "eagle-import") (part "RESISTOR_0603"))
    )
    (comp (ref "R36")
      (value "10k")
      (footprint "eagle-import:_0603")
      (description "RES 10K OHM 5%% 1/10W 0603")
      (fields
        (field (name "MANUFACTURER") "Stackpole Electronics Inc")
        (field (name "MANUFACTURERPARTNUMBER") "RMCF0603JT10K0")
      )
      (libsource (lib "eagle-import") (part "RESISTOR_0603"))
    )
    (comp (ref "R37")
      (value "10k")
      (footprint "eagle-import:_0603")
      (description "RES 10K OHM 5%% 1/10W 0603")
      (fields
        (field (name "MANUFACTURER") "Stackpole Electronics Inc")
        (field (name "MANUFACTURERPARTNUMBER") "RMCF0603JT10K0")
      )
      (libsource (lib "eagle-import") (part "RESISTOR_0603"))
    )
    (comp (ref "R38")
      (value "120")
      (footprint "eagle-import:_0603")
      (description "RES 120 OHM 5%% 1/10W 0603")
      (fields
        (field (name "MANUFACTURER") "Stackpole Electronics Inc")
        (field (name "MANUFACTURERPARTNUMBER") "RMCF0603JT120R")
      )
      (libsource (lib "eagle-import") (part "RESISTOR_0603"))
    )
    (comp (ref "R39")
      (value "120")
      (footprint "eagle-import:_0603")
      (description "RES 120 OHM 5%% 1/10W 0603")
      (fields
        (field (name "MANUFACTURER") "Stackpole Electronics Inc")
        (field (name "MANUFACTURERPARTNUMBER") "RMCF0603JT120R")
      )
      (libsource (lib "eagle-import") (part "RESISTOR_0603"))
    )
    (comp (ref "R40")
      (value "330")
      (footprint "eagle-import:_0603")
      (description "RES SMD 330 OHM 1%% 1/10W 0603")
      (fields
        (field (name "MANUFACTURER") "Yageo")
        (field (name "MANUFACTURERPARTNUMBER") "RC0603FR-07330RL")
      )
      (libsource (lib "eagle-import") (part "RESISTOR_0603"))
    )
    (comp (ref "R41")
      (value "330")
      (footprint "eagle-import:_0603")
      (description "RES SMD 330 OHM 1%% 1/10W 0603")
      (fields
        (field (name "MANUFACTURER") "Yageo")
        (field (name "MANUFACTURERPARTNUMBER") "RC0603FR-07330RL")
      )
      (libsource (lib "eagle-import") (part "RESISTOR_0603"))
    )
    (comp (ref "R42")
      (value "1k")
      (footprint "eagle-import:_0603")
      (description "RES 1K OHM 5%% 1/10W 0603")
      (fields
        (field (name "MANUFACTURER") "Stackpole Electronics Inc")
        (field (name "MANUFACTURERPARTNUMBER") "RMCF0603JT1K00")
      )
      (libsource (lib "eagle-import") (part "RESISTOR_0603"))
    )
    (comp (ref "R43")
      (value "1k")
      (footprint "eagle-import:_0603")
      (description "RES 1K OHM 5%% 1/10W 0603")
      (fields
        (field (name "MANUFACTURER") "Stackpole Electronics Inc")
        (field (name "MANUFACTURERPARTNUMBER") "RMCF0603JT1K00")
      )
      (libsource (lib "eagle-import") (part "RESISTOR_0603"))
    )
    (comp (ref "R44")
      (value "DNP")
      (footprint "eagle-import:_0603")
      (description "RES SMD 0 OHM JUMPER 1/10W 0603")
      (fields
        (field (name "MANUFACTURER") "Panasonic Electronic Components")
        (field (name "MANUFACTURERPARTNUMBER") "ERJ-3GEY0R00V")
      )
      (libsource (lib "eagle-import") (part "RESISTOR_0603"))
    )
    (comp (ref "R45")
      (value "DNP")
      (footprint "eagle-import:_0603")
      (description "RES SMD 0 OHM JUMPER 1/10W 0603")
      (fields
        (field (name "MANUFACTURER") "Panasonic Electronic Components")
        (field (name "MANUFACTURERPARTNUMBER") "ERJ-3GEY0R00V")
      )
      (libsource (lib "eagle-import") (part "RESISTOR_0603"))
    )
    (comp (ref "R46")
      (value "DNP")
      (footprint "eagle-import:_0603")
      (description "RES SMD 0 OHM JUMPER 1/10W 0603")
      (fields
        (field (name "MANUFACTURER") "Panasonic Electronic Components")
        (field (name "MANUFACTURERPARTNUMBER") "ERJ-3GEY0R00V")
      )
      (libsource (lib "eagle-import") (part "RESISTOR_0603"))
    )
    (comp (ref "T1")
      (value "BC847C")
      (footprint "eagle-import:SOT23-BEC")
      (description "TRANS NPN 45V 0.1A SOT23")
      (fields
        (field (name "MANUFACTURER") "Nexperia USA Inc.")
        (field (name "MANUFACTURERPARTNUMBER") "BC847C,215")
      )
      (libsource (lib "eagle-import") (part "-NPN-SOT23-BECBC847C"))
    )
    (comp (ref "T2")
      (value "BC847C")
      (footprint "eagle-import:SOT23-BEC")
      (description "TRANS NPN 45V 0.1A SOT23")
      (fields
        (field (name "MANUFACTURER") "Nexperia USA Inc.")
        (field (name "MANUFACTURERPARTNUMBER") "BC847C,215")
      )
      (libsource (lib "eagle-import") (part "-NPN-SOT23-BECBC847C"))
    )
    (comp (ref "TP1")
      (value "TPTP12R")
      (footprint "eagle-import:TP12R")
      (description "NO DESCRIPTION")
      (fields
        (field (name "MANUFACTURER") "UNKNOWN MANUFACTURER")
        (field (name "MANUFACTURERPARTNUMBER") "UNKNOWN MANUFACTURER PART NUMBER")
      )
      (libsource (lib "eagle-import") (part "TPTP12R"))
    )
    (comp (ref "TP2")
      (value "TPTP12R")
      (footprint "eagle-import:TP12R")
      (description "NO DESCRIPTION")
      (fields
        (field (name "MANUFACTURER") "UNKNOWN MANUFACTURER")
        (field (name "MANUFACTURERPARTNUMBER") "UNKNOWN MANUFACTURER PART NUMBER")
      )
      (libsource (lib "eagle-import") (part "TPTP12R"))
    )
    (comp (ref "TP3")
      (value "TPTP12R")
      (footprint "eagle-import:TP12R")
      (description "NO DESCRIPTION")
      (fields
        (field (name "MANUFACTURER") "UNKNOWN MANUFACTURER")
        (field (name "MANUFACTURERPARTNUMBER") "UNKNOWN MANUFACTURER PART NUMBER")
      )
      (libsource (lib "eagle-import") (part "TPTP12R"))
    )
    (comp (ref "TP4")
      (value "TPTP12R")
      (footprint "eagle-import:TP12R")
      (description "NO DESCRIPTION")
      (fields
        (field (name "MANUFACTURER") "UNKNOWN MANUFACTURER")
        (field (name "MANUFACTURERPARTNUMBER") "UNKNOWN MANUFACTURER PART NUMBER")
      )
      (libsource (lib "eagle-import") (part "TPTP12R"))
    )
    (comp (ref "TR1")
      (value "PULSE_T1094NL")
      (footprint "eagle-import:PULSE_BH")
      (description "TRANSFORMER TELECOM DUAL T1/E2")
      (fields
        (field (name "MANUFACTURER") "Pulse Electronics Network")
        (field (name "MANUFACTURERPARTNUMBER") "T1094NL")
      )
      (libsource (lib "eagle-import") (part "PULSE_T1094NL"))
    )
    (comp (ref "TR2")
      (value "PULSE_T1094NL")
      (footprint "eagle-import:PULSE_BH")
      (description "TRANSFORMER TELECOM DUAL T1/E2")
      (fields
        (field (name "MANUFACTURER") "Pulse Electronics Network")
        (field (name "MANUFACTURERPARTNUMBER") "T1094NL")
      )
      (libsource (lib "eagle-import") (part "PULSE_T1094NL"))
    )
    (comp (ref "U4")
      (value "IDT82V2081")
      (footprint "eagle-import:TQFP44")
      (description "IC TELECOM INTERFACE 44TQFP")
      (fields
        (field (name "CLASS") "IC")
        (field (name "LINK") "https://www.digikey.de/product-detail/de/renesas-electronics-america-inc/82V2081PPG/800-2347-ND")
        (field (name "MANUFACTURER") "Renesas Electronics America Inc")
        (field (name "MANUFACTURERPARTNUMBER") "82V2081PPG")
        (field (name "POPULATED") "TRUE")
        (field (name "ROHSCERTIFICATE") "RoHS3-konform")
        (field (name "SOURCE") "DIGIKEY")
        (field (name "SOURCEPARTNUMBER") "800-2347-ND")
      )
      (libsource (lib "eagle-import") (part "IDT82V2081"))
    )
    (comp (ref "U5")
      (value "IDT82V2081")
      (footprint "eagle-import:TQFP44")
      (description "IC TELECOM INTERFACE 44TQFP")
      (fields
        (field (name "CLASS") "IC")
        (field (name "LINK") "https://www.digikey.de/product-detail/de/renesas-electronics-america-inc/82V2081PPG/800-2347-ND")
        (field (name "MANUFACTURER") "Renesas Electronics America Inc")
        (field (name "MANUFACTURERPARTNUMBER") "82V2081PPG")
        (field (name "POPULATED") "TRUE")
        (field (name "ROHSCERTIFICATE") "RoHS3-konform")
        (field (name "SOURCE") "DIGIKEY")
        (field (name "SOURCEPARTNUMBER") "800-2347-ND")
      )
      (libsource (lib "eagle-import") (part "IDT82V2081"))
    )
    (comp (ref "U6")
      (value "2.048 Mhz")
      (footprint "eagle-import:HC73")
      (description "XTAL OSC XO 2.0480MHZ HCMOS SMD")
      (fields
        (field (name "MANUFACTURER") "Renesas Electronics America Inc")
        (field (name "MANUFACTURERPARTNUMBER") "XLH736002.048000I")
      )
      (libsource (lib "eagle-import") (part "FOX_FXO-HC73"))
    )
    (comp (ref "U7")
      (value "1.544 MHz")
      (footprint "eagle-import:HC73")
      (description "NO DESCRIPTION")
      (fields
        (field (name "MANUFACTURER") "UNKNOWN MANUFACTURER")
        (field (name "MANUFACTURERPARTNUMBER") "UNKNOWN MANUFACTURER PART NUMBER")
      )
      (libsource (lib "eagle-import") (part "FOX_FXO-HC73"))
    )
  )
  (nets
    (net (code "6") (name "BOOT_SW") (class "Default")
      (node (ref "SW1") (pin "2") (pinfunction "2_2") (pintype "passive"))
      (node (ref "U1") (pin "25") (pinfunction "IOT_36B_25") (pintype "bidirectional"))
    )
    (net (code "7") (name "CDONE") (class "Default")
      (node (ref "CDONE") (pin "A") (pinfunction "A_A") (pintype "passive"))
      (node (ref "JP1") (pin "6") (pinfunction "6_6") (pintype "passive"))
      (node (ref "R14") (pin "2") (pinfunction "2_2") (pintype "passive"))
      (node (ref "U1") (pin "7") (pinfunction "CDONE_7") (pintype "output"))
    )
    (net (code "8") (name "CLK_12M") (class "Default")
      (node (ref "IC4") (pin "3") (pinfunction "OUT_3") (pintype "output"))
      (node (ref "U1") (pin "20") (pinfunction "IOB_25B_G3_20") (pintype "bidirectional"))
    )
    (net (code "9") (name "GND") (class "Default")
      (node (ref "C1") (pin "1") (pinfunction "1_1") (pintype "passive"))
      (node (ref "C10") (pin "2") (pinfunction "2_2") (pintype "passive"))
      (node (ref "C11") (pin "2") (pinfunction "2_2") (pintype "passive"))
      (node (ref "C12") (pin "2") (pinfunction "2_2") (pintype "passive"))
      (node (ref "C13") (pin "2") (pinfunction "2_2") (pintype "passive"))
      (node (ref "C14") (pin "2") (pinfunction "2_2") (pintype "passive"))
      (node (ref "C15") (pin "2") (pinfunction "2_2") (pintype "passive"))
      (node (ref "C16") (pin "2") (pinfunction "2_2") (pintype "passive"))
      (node (ref "C17") (pin "2") (pinfunction "2_2") (pintype "passive"))
      (node (ref "C18") (pin "2") (pinfunction "2_2") (pintype "passive"))
      (node (ref "C19") (pin "2") (pinfunction "2_2") (pintype "passive"))
      (node (ref "C2") (pin "1") (pinfunction "1_1") (pintype "passive"))
      (node (ref "C20") (pin "2") (pinfunction "2_2") (pintype "passive"))
      (node (ref "C21") (pin "2") (pinfunction "2_2") (pintype "passive"))
      (node (ref "C22") (pin "2") (pinfunction "2_2") (pintype "passive"))
      (node (ref "C23") (pin "2") (pinfunction "2_2") (pintype "passive"))
      (node (ref "C24") (pin "2") (pinfunction "2_2") (pintype "passive"))
      (node (ref "C25") (pin "1") (pinfunction "1_1") (pintype "passive"))
      (node (ref "C26") (pin "1") (pinfunction "1_1") (pintype "passive"))
      (node (ref "C27") (pin "1") (pinfunction "1_1") (pintype "passive"))
      (node (ref "C28") (pin "1") (pinfunction "1_1") (pintype "passive"))
      (node (ref "C29") (pin "1") (pinfunction "1_1") (pintype "passive"))
      (node (ref "C3") (pin "1") (pinfunction "1_1") (pintype "passive"))
      (node (ref "C30") (pin "1") (pinfunction "1_1") (pintype "passive"))
      (node (ref "C4") (pin "1") (pinfunction "1_1") (pintype "passive"))
      (node (ref "C5") (pin "1") (pinfunction "1_1") (pintype "passive"))
      (node (ref "C6") (pin "1") (pinfunction "1_1") (pintype "passive"))
      (node (ref "C7") (pin "1") (pinfunction "1_1") (pintype "passive"))
      (node (ref "C8") (pin "1") (pinfunction "1_1") (pintype "passive"))
      (node (ref "C9") (pin "2") (pinfunction "2_2") (pintype "passive"))
      (node (ref "CDONE") (pin "C") (pinfunction "C_C") (pintype "passive"))
      (node (ref "D5") (pin "2") (pinfunction "A_2") (pintype "passive"))
      (node (ref "D6") (pin "2") (pinfunction "A_2") (pintype "passive"))
      (node (ref "D7") (pin "2") (pinfunction "A_2") (pintype "passive"))
      (node (ref "D8") (pin "2") (pinfunction "A_2") (pintype "passive"))
      (node (ref "IC1") (pin "1") (pinfunction "GND_1") (pintype "power_in"))
      (node (ref "IC2") (pin "4") (pinfunction "GND_4") (pintype "power_in"))
      (node (ref "IC3") (pin "2") (pinfunction "GND_2") (pintype "power_in"))
      (node (ref "IC3") (pin "4") (pinfunction "GND_4") (pintype "power_in"))
      (node (ref "IC4") (pin "2") (pinfunction "GND_2") (pintype "passive"))
      (node (ref "JP1") (pin "8") (pinfunction "8_8") (pintype "passive"))
      (node (ref "R11") (pin "1") (pinfunction "1_1") (pintype "passive"))
      (node (ref "R15") (pin "2") (pinfunction "2_2") (pintype "passive"))
      (node (ref "R16") (pin "2") (pinfunction "2_2") (pintype "passive"))
      (node (ref "R17") (pin "2") (pinfunction "2_2") (pintype "passive"))
      (node (ref "R18") (pin "2") (pinfunction "2_2") (pintype "passive"))
      (node (ref "R19") (pin "2") (pinfunction "2_2") (pintype "passive"))
      (node (ref "R20") (pin "2") (pinfunction "2_2") (pintype "passive"))
      (node (ref "R21") (pin "2") (pinfunction "2_2") (pintype "passive"))
      (node (ref "R22") (pin "2") (pinfunction "2_2") (pintype "passive"))
      (node (ref "R23") (pin "2") (pinfunction "2_2") (pintype "passive"))
      (node (ref "R25") (pin "2") (pinfunction "2_2") (pintype "passive"))
      (node (ref "R26") (pin "2") (pinfunction "2_2") (pintype "passive"))
      (node (ref "R27") (pin "2") (pinfunction "2_2") (pintype "passive"))
      (node (ref "R28") (pin "2") (pinfunction "2_2") (pintype "passive"))
      (node (ref "R29") (pin "2") (pinfunction "2_2") (pintype "passive"))
      (node (ref "R30") (pin "2") (pinfunction "2_2") (pintype "passive"))
      (node (ref "R31") (pin "2") (pinfunction "2_2") (pintype "passive"))
      (node (ref "R32") (pin "2") (pinfunction "2_2") (pintype "passive"))
      (node (ref "R34") (pin "1") (pinfunction "1_1") (pintype "passive"))
      (node (ref "R35") (pin "1") (pinfunction "1_1") (pintype "passive"))
      (node (ref "R45") (pin "2") (pinfunction "2_2") (pintype "passive"))
      (node (ref "R46") (pin "1") (pinfunction "1_1") (pintype "passive"))
      (node (ref "SW1") (pin "1") (pinfunction "1_1") (pintype "passive"))
      (node (ref "SW1") (pin "3") (pinfunction "3_3") (pintype "passive"))
      (node (ref "T1") (pin "E") (pinfunction "E_E") (pintype "passive"))
      (node (ref "T2") (pin "E") (pinfunction "E_E") (pintype "passive"))
      (node (ref "U1") (pin "EXP") (pinfunction "GND_EXP") (pintype "bidirectional"))
      (node (ref "U2") (pin "2") (pinfunction "GND_2") (pintype "passive"))
      (node (ref "U3") (pin "2") (pinfunction "GND_2") (pintype "passive"))
      (node (ref "U4") (pin "10") (pinfunction "GNDD_10") (pintype "power_in"))
      (node (ref "U4") (pin "11") (pinfunction "RCLKE_11") (pintype "input"))
      (node (ref "U4") (pin "13") (pinfunction "THZ_13") (pintype "input"))
      (node (ref "U4") (pin "14") (pinfunction "JA0_14") (pintype "input"))
      (node (ref "U4") (pin "15") (pinfunction "JA1_15") (pintype "input"))
      (node (ref "U4") (pin "17") (pinfunction "MODE1_17") (pintype "input"))
      (node (ref "U4") (pin "18") (pinfunction "GNDIO_18") (pintype "power_in"))
      (node (ref "U4") (pin "22") (pinfunction "~{RD/DS/SCLKE}_22") (pintype "input"))
      (node (ref "U4") (pin "38") (pinfunction "GNDT_38") (pintype "power_in"))
      (node (ref "U4") (pin "39") (pinfunction "GNDA_39") (pintype "power_in"))
      (node (ref "U5") (pin "10") (pinfunction "GNDD_10") (pintype "power_in"))
      (node (ref "U5") (pin "11") (pinfunction "RCLKE_11") (pintype "input"))
      (node (ref "U5") (pin "13") (pinfunction "THZ_13") (pintype "input"))
      (node (ref "U5") (pin "14") (pinfunction "JA0_14") (pintype "input"))
      (node (ref "U5") (pin "15") (pinfunction "JA1_15") (pintype "input"))
      (node (ref "U5") (pin "17") (pinfunction "MODE1_17") (pintype "input"))
      (node (ref "U5") (pin "18") (pinfunction "GNDIO_18") (pintype "power_in"))
      (node (ref "U5") (pin "22") (pinfunction "~{RD/DS/SCLKE}_22") (pintype "input"))
      (node (ref "U5") (pin "38") (pinfunction "GNDT_38") (pintype "power_in"))
      (node (ref "U5") (pin "39") (pinfunction "GNDA_39") (pintype "power_in"))
      (node (ref "U6") (pin "P$2") (pinfunction "GND_P$2") (pintype "power_in"))
      (node (ref "U7") (pin "P$2") (pinfunction "GND_P$2") (pintype "power_in"))
      (node (ref "X1") (pin "5") (pinfunction "5_5") (pintype "input"))
      (node (ref "X2") (pin "1") (pinfunction "RING_1") (pintype "passive"))
    )
    (net (code "10") (name "IOB_32A_SPI_SO") (class "Default")
      (node (ref "IC2") (pin "5") (pinfunction "SI(D0)_5") (pintype "bidirectional"))
      (node (ref "JP1") (pin "2") (pinfunction "2_2") (pintype "passive"))
      (node (ref "U1") (pin "14") (pinfunction "IOB_32A_SPI_SO_14") (pintype "bidirectional"))
    )
    (net (code "11") (name "IOB_33B_SPI_SI") (class "Default")
      (node (ref "IC2") (pin "2") (pinfunction "SO(D1)_2") (pintype "bidirectional"))
      (node (ref "JP1") (pin "3") (pinfunction "3_3") (pintype "passive"))
      (node (ref "U1") (pin "17") (pinfunction "IOB_33B_SPI_SI_17") (pintype "bidirectional"))
    )
    (net (code "12") (name "IOB_34A_SPI_SCK") (class "Default")
      (node (ref "IC2") (pin "6") (pinfunction "SCK_6") (pintype "input"))
      (node (ref "JP1") (pin "4") (pinfunction "4_4") (pintype "passive"))
      (node (ref "R10") (pin "1") (pinfunction "1_1") (pintype "passive"))
      (node (ref "U1") (pin "15") (pinfunction "IOB_34A_SPI_SCK_15") (pintype "bidirectional"))
    )
    (net (code "13") (name "IOB_35B_SPI_SS") (class "Default")
      (node (ref "IC2") (pin "1") (pinfunction "~{CS}_1") (pintype "input"))
      (node (ref "JP1") (pin "5") (pinfunction "5_5") (pintype "passive"))
      (node (ref "R8") (pin "1") (pinfunction "1_1") (pintype "passive"))
      (node (ref "U1") (pin "16") (pinfunction "IOB_35B_SPI_SS_16") (pintype "bidirectional"))
    )
    (net (code "14") (name "IO_A0") (class "Default")
      (node (ref "U1") (pin "31") (pinfunction "IOT_42B_31") (pintype "bidirectional"))
      (node (ref "U4") (pin "24") (pinfunction "SDI/WR/RW_24") (pintype "input"))
      (node (ref "U5") (pin "24") (pinfunction "SDI/WR/RW_24") (pintype "input"))
    )
    (net (code "15") (name "IO_A1") (class "Default")
      (node (ref "U1") (pin "32") (pinfunction "IOT_43A_32") (pintype "bidirectional"))
      (node (ref "U4") (pin "23") (pinfunction "SDO/~{ACK/RDY}_23") (pintype "output"))
      (node (ref "U5") (pin "23") (pinfunction "SDO/~{ACK/RDY}_23") (pintype "output"))
    )
    (net (code "16") (name "IO_A2") (class "Default")
      (node (ref "U1") (pin "34") (pinfunction "IOT_44B_34") (pintype "bidirectional"))
      (node (ref "U4") (pin "25") (pinfunction "SCLK/ALE/AS_25") (pintype "input"))
      (node (ref "U5") (pin "25") (pinfunction "SCLK/ALE/AS_25") (pintype "input"))
    )
    (net (code "17") (name "IO_A3") (class "Default")
      (node (ref "U1") (pin "38") (pinfunction "IOT_50B_38") (pintype "bidirectional"))
      (node (ref "U3") (pin "3") (pinfunction "1B_3") (pintype "passive"))
    )
    (net (code "18") (name "IO_A4") (class "Default")
      (node (ref "U1") (pin "42") (pinfunction "IOT_51A_42") (pintype "bidirectional"))
      (node (ref "U4") (pin "21") (pinfunction "~{CS}_21") (pintype "input"))
    )
    (net (code "19") (name "IO_A5") (class "Default")
      (node (ref "U1") (pin "43") (pinfunction "IOT_49A_43") (pintype "bidirectional"))
      (node (ref "U5") (pin "21") (pinfunction "~{CS}_21") (pintype "input"))
    )
    (net (code "20") (name "IO_B0") (class "Default")
      (node (ref "U1") (pin "44") (pinfunction "IOB_3B_G6_44") (pintype "bidirectional"))
      (node (ref "U4") (pin "4") (pinfunction "RCLK_4") (pintype "output"))
    )
    (net (code "21") (name "IO_B1") (class "Default")
      (node (ref "U1") (pin "45") (pinfunction "IOB_5B_45") (pintype "bidirectional"))
      (node (ref "U4") (pin "5") (pinfunction "RD/RDP_5") (pintype "output"))
    )
    (net (code "22") (name "IO_B2") (class "Default")
      (node (ref "U1") (pin "46") (pinfunction "IOB_0A_46") (pintype "bidirectional"))
      (node (ref "U5") (pin "4") (pinfunction "RCLK_4") (pintype "output"))
    )
    (net (code "23") (name "IO_B3") (class "Default")
      (node (ref "U1") (pin "47") (pinfunction "IOB_2A_47") (pintype "bidirectional"))
      (node (ref "U5") (pin "5") (pinfunction "RD/RDP_5") (pintype "output"))
    )
    (net (code "24") (name "LOS0") (class "Default")
      (node (ref "R36") (pin "2") (pinfunction "2_2") (pintype "passive"))
      (node (ref "U4") (pin "7") (pinfunction "LOS_7") (pintype "output"))
    )
    (net (code "25") (name "LOS1") (class "Default")
      (node (ref "R37") (pin "2") (pinfunction "2_2") (pintype "passive"))
      (node (ref "U5") (pin "7") (pinfunction "LOS_7") (pintype "output"))
    )
    (net (code "26") (name "MCLK") (class "Default")
      (node (ref "R44") (pin "2") (pinfunction "2_2") (pintype "passive"))
      (node (ref "U4") (pin "9") (pinfunction "MCLK_9") (pintype "power_in"))
      (node (ref "U5") (pin "9") (pinfunction "MCLK_9") (pintype "power_in"))
      (node (ref "U6") (pin "P$3") (pinfunction "OUT_P$3") (pintype "output"))
      (node (ref "U7") (pin "P$3") (pinfunction "OUT_P$3") (pintype "output"))
    )
    (net (code "27") (name "Net-(D1-A)") (class "Default")
      (node (ref "D1") (pin "2") (pinfunction "A_2") (pintype "passive"))
      (node (ref "D5") (pin "1") (pinfunction "C_1") (pintype "passive"))
      (node (ref "R38") (pin "2") (pinfunction "2_2") (pintype "passive"))
      (node (ref "TP1") (pin "TP") (pinfunction "TP_TP") (pintype "input"))
      (node (ref "TR1") (pin "1") (pinfunction "P$4_1") (pintype "bidirectional"))
      (node (ref "U4") (pin "41") (pinfunction "RTIP_41") (pintype "input"))
    )
    (net (code "28") (name "Net-(D2-A)") (class "Default")
      (node (ref "D2") (pin "2") (pinfunction "A_2") (pintype "passive"))
      (node (ref "D6") (pin "1") (pinfunction "C_1") (pintype "passive"))
      (node (ref "R38") (pin "1") (pinfunction "1_1") (pintype "passive"))
      (node (ref "TP2") (pin "TP") (pinfunction "TP_TP") (pintype "input"))
      (node (ref "TR1") (pin "3") (pinfunction "P$6_3") (pintype "bidirectional"))
      (node (ref "U4") (pin "40") (pinfunction "RRING_40") (pintype "input"))
    )
    (net (code "29") (name "Net-(D3-A)") (class "Default")
      (node (ref "D3") (pin "2") (pinfunction "A_2") (pintype "passive"))
      (node (ref "D7") (pin "1") (pinfunction "C_1") (pintype "passive"))
      (node (ref "R39") (pin "2") (pinfunction "2_2") (pintype "passive"))
      (node (ref "TP3") (pin "TP") (pinfunction "TP_TP") (pintype "input"))
      (node (ref "TR2") (pin "1") (pinfunction "P$4_1") (pintype "bidirectional"))
      (node (ref "U5") (pin "41") (pinfunction "RTIP_41") (pintype "input"))
    )
    (net (code "30") (name "Net-(D4-A)") (class "Default")
      (node (ref "D4") (pin "2") (pinfunction "A_2") (pintype "passive"))
      (node (ref "D8") (pin "1") (pinfunction "C_1") (pintype "passive"))
      (node (ref "R39") (pin "1") (pinfunction "1_1") (pintype "passive"))
      (node (ref "TP4") (pin "TP") (pinfunction "TP_TP") (pintype "input"))
      (node (ref "TR2") (pin "3") (pinfunction "P$6_3") (pintype "bidirectional"))
      (node (ref "U5") (pin "40") (pinfunction "RRING_40") (pintype "input"))
    )
    (net (code "31") (name "Net-(IC4-OE{slash}~{ST})") (class "Default")
      (node (ref "IC4") (pin "1") (pinfunction "OE/~{ST}_1") (pintype "input"))
      (node (ref "R13") (pin "1") (pinfunction "1_1") (pintype "passive"))
    )
    (net (code "32") (name "Net-(J1A-1)") (class "Default")
      (node (ref "J1") (pin "1-1") (pinfunction "1_1-1") (pintype "passive"))
      (node (ref "J1") (pin "2-1") (pinfunction "1_2-1") (pintype "passive"))
      (node (ref "TR1") (pin "14") (pinfunction "P$3_14") (pintype "bidirectional"))
    )
    (net (code "33") (name "Net-(J1A-2)") (class "Default")
      (node (ref "J1") (pin "1-2") (pinfunction "2_1-2") (pintype "passive"))
      (node (ref "J1") (pin "2-2") (pinfunction "2_2-2") (pintype "passive"))
      (node (ref "R42") (pin "1") (pinfunction "1_1") (pintype "passive"))
    )
    (net (code "34") (name "Net-(J1A-3)") (class "Default")
      (node (ref "J1") (pin "1-3") (pinfunction "3_1-3") (pintype "passive"))
      (node (ref "J1") (pin "2-3") (pinfunction "3_2-3") (pintype "passive"))
    )
    (net (code "35") (name "Net-(J1A-4)") (class "Default")
      (node (ref "J1") (pin "1-4") (pinfunction "4_1-4") (pintype "passive"))
      (node (ref "J1") (pin "2-4") (pinfunction "4_2-4") (pintype "passive"))
      (node (ref "TR2") (pin "14") (pinfunction "P$3_14") (pintype "bidirectional"))
    )
    (net (code "36") (name "Net-(J1A-5)") (class "Default")
      (node (ref "J1") (pin "1-5") (pinfunction "5_1-5") (pintype "passive"))
      (node (ref "J1") (pin "2-5") (pinfunction "5_2-5") (pintype "passive"))
      (node (ref "R43") (pin "1") (pinfunction "1_1") (pintype "passive"))
    )
    (net (code "37") (name "Net-(J1A-6)") (class "Default")
      (node (ref "J1") (pin "1-6") (pinfunction "6_1-6") (pintype "passive"))
      (node (ref "J1") (pin "2-6") (pinfunction "6_2-6") (pintype "passive"))
    )
    (net (code "38") (name "Net-(J1A-7)") (class "Default")
      (node (ref "J1") (pin "1-7") (pinfunction "7_1-7") (pintype "passive"))
      (node (ref "J1") (pin "2-7") (pinfunction "7_2-7") (pintype "passive"))
    )
    (net (code "39") (name "Net-(J1A-8)") (class "Default")
      (node (ref "J1") (pin "1-8") (pinfunction "8_1-8") (pintype "passive"))
      (node (ref "J1") (pin "2-8") (pinfunction "8_2-8") (pintype "passive"))
    )
    (net (code "40") (name "Net-(L1-Pad1)") (class "Default")
      (node (ref "L1") (pin "1") (pinfunction "1_1") (pintype "bidirectional"))
      (node (ref "R7") (pin "2") (pinfunction "2_2") (pintype "passive"))
    )
    (net (code "41") (name "Net-(L1-Pad4)") (class "Default")
      (node (ref "L1") (pin "4") (pinfunction "4_4") (pintype "bidirectional"))
      (node (ref "R6") (pin "2") (pinfunction "2_2") (pintype "passive"))
    )
    (net (code "42") (name "Net-(LED1-BLUE)") (class "Default")
      (node (ref "LED1") (pin "3") (pinfunction "BLUE_3") (pintype "bidirectional"))
      (node (ref "R2") (pin "1") (pinfunction "1_1") (pintype "passive"))
      (node (ref "R4") (pin "1") (pinfunction "1_1") (pintype "passive"))
    )
    (net (code "43") (name "Net-(LED1-GRN)") (class "Default")
      (node (ref "LED1") (pin "4") (pinfunction "GRN_4") (pintype "bidirectional"))
      (node (ref "U1") (pin "40") (pinfunction "RGB1_40") (pintype "bidirectional"))
    )
    (net (code "44") (name "Net-(LED1-RED)") (class "Default")
      (node (ref "LED1") (pin "1") (pinfunction "RED_1") (pintype "bidirectional"))
      (node (ref "R3") (pin "2") (pinfunction "2_2") (pintype "passive"))
      (node (ref "R5") (pin "2") (pinfunction "2_2") (pintype "passive"))
    )
    (net (code "45") (name "Net-(LOS1-C)") (class "Default")
      (node (ref "LOS1") (pin "K") (pinfunction "C_K") (pintype "passive"))
      (node (ref "R40") (pin "1") (pinfunction "1_1") (pintype "passive"))
    )
    (net (code "46") (name "Net-(LOS2-C)") (class "Default")
      (node (ref "LOS2") (pin "K") (pinfunction "C_K") (pintype "passive"))
      (node (ref "R41") (pin "1") (pinfunction "1_1") (pintype "passive"))
    )
    (net (code "47") (name "Net-(PWR-C)") (class "Default")
      (node (ref "PWR") (pin "K") (pinfunction "C_K") (pintype "passive"))
      (node (ref "R15") (pin "1") (pinfunction "1_1") (pintype "passive"))
    )
    (net (code "48") (name "Net-(R11-Pad2)") (class "Default")
      (node (ref "R11") (pin "2") (pinfunction "2_2") (pintype "passive"))
      (node (ref "R12") (pin "1") (pinfunction "1_1") (pintype "passive"))
    )
    (net (code "49") (name "Net-(R36-Pad1)") (class "Default")
      (node (ref "R36") (pin "1") (pinfunction "1_1") (pintype "passive"))
      (node (ref "T1") (pin "B") (pinfunction "B_B") (pintype "passive"))
    )
    (net (code "50") (name "Net-(R37-Pad1)") (class "Default")
      (node (ref "R37") (pin "1") (pinfunction "1_1") (pintype "passive"))
      (node (ref "T2") (pin "B") (pinfunction "B_B") (pintype "passive"))
    )
    (net (code "51") (name "Net-(R40-Pad2)") (class "Default")
      (node (ref "R40") (pin "2") (pinfunction "2_2") (pintype "passive"))
      (node (ref "T1") (pin "C") (pinfunction "C_C") (pintype "passive"))
    )
    (net (code "52") (name "Net-(R41-Pad2)") (class "Default")
      (node (ref "R41") (pin "2") (pinfunction "2_2") (pintype "passive"))
      (node (ref "T2") (pin "C") (pinfunction "C_C") (pintype "passive"))
    )
    (net (code "53") (name "Net-(TR1A-P$1)") (class "Default")
      (node (ref "R42") (pin "2") (pinfunction "2_2") (pintype "passive"))
      (node (ref "TR1") (pin "16") (pinfunction "P$1_16") (pintype "bidirectional"))
    )
    (net (code "54") (name "Net-(TR2A-P$1)") (class "Default")
      (node (ref "R43") (pin "2") (pinfunction "2_2") (pintype "passive"))
      (node (ref "TR2") (pin "16") (pinfunction "P$1_16") (pintype "bidirectional"))
    )
    (net (code "55") (name "Net-(U1-RGB0)") (class "Default")
      (node (ref "R4") (pin "2") (pinfunction "2_2") (pintype "passive"))
      (node (ref "R5") (pin "1") (pinfunction "1_1") (pintype "passive"))
      (node (ref "U1") (pin "39") (pinfunction "RGB0_39") (pintype "bidirectional"))
    )
    (net (code "56") (name "Net-(U1-RGB2)") (class "Default")
      (node (ref "R2") (pin "2") (pinfunction "2_2") (pintype "passive"))
      (node (ref "R3") (pin "1") (pinfunction "1_1") (pintype "passive"))
      (node (ref "U1") (pin "41") (pinfunction "RGB2_41") (pintype "bidirectional"))
    )
    (net (code "57") (name "Net-(U1-VCC_PLL)") (class "Default")
      (node (ref "C7") (pin "2") (pinfunction "2_2") (pintype "passive"))
      (node (ref "C8") (pin "2") (pinfunction "2_2") (pintype "passive"))
      (node (ref "R1") (pin "1") (pinfunction "1_1") (pintype "passive"))
      (node (ref "U1") (pin "29") (pinfunction "VCC_PLL_29") (pintype "power_in"))
    )
    (net (code "58") (name "Net-(U2-1A)") (class "Default")
      (node (ref "U2") (pin "1") (pinfunction "1A_1") (pintype "passive"))
      (node (ref "X1") (pin "3") (pinfunction "3_3") (pintype "input"))
    )
    (net (code "59") (name "Net-(U2-1B)") (class "Default")
      (node (ref "L1") (pin "2") (pinfunction "2_2") (pintype "bidirectional"))
      (node (ref "R9") (pin "2") (pinfunction "2_2") (pintype "passive"))
      (node (ref "U2") (pin "3") (pinfunction "1B_3") (pintype "passive"))
    )
    (net (code "60") (name "Net-(U2-2A)") (class "Default")
      (node (ref "U2") (pin "6") (pinfunction "2A_6") (pintype "passive"))
      (node (ref "X1") (pin "2") (pinfunction "2_2") (pintype "input"))
    )
    (net (code "61") (name "Net-(U2-2B)") (class "Default")
      (node (ref "L1") (pin "3") (pinfunction "3_3") (pintype "bidirectional"))
      (node (ref "U2") (pin "4") (pinfunction "2B_4") (pintype "passive"))
    )
    (net (code "62") (name "Net-(U3-1A)") (class "Default")
      (node (ref "U3") (pin "1") (pinfunction "1A_1") (pintype "passive"))
      (node (ref "X2") (pin "3") (pinfunction "MIDDLE_3") (pintype "passive"))
    )
    (net (code "63") (name "Net-(U4D-EQ{slash}AD3)") (class "Default")
      (node (ref "R20") (pin "1") (pinfunction "1_1") (pintype "passive"))
      (node (ref "U4") (pin "29") (pinfunction "EQ/AD3_29") (pintype "input"))
    )
    (net (code "64") (name "Net-(U4D-PATT0{slash}AD0)") (class "Default")
      (node (ref "R23") (pin "1") (pinfunction "1_1") (pintype "passive"))
      (node (ref "U4") (pin "26") (pinfunction "PATT0/AD0_26") (pintype "input"))
    )
    (net (code "65") (name "Net-(U4D-PATT1{slash}AD1)") (class "Default")
      (node (ref "R22") (pin "1") (pinfunction "1_1") (pintype "passive"))
      (node (ref "U4") (pin "27") (pinfunction "PATT1/AD1_27") (pintype "input"))
    )
    (net (code "66") (name "Net-(U4D-PULS0{slash}AD4)") (class "Default")
      (node (ref "R19") (pin "1") (pinfunction "1_1") (pintype "passive"))
      (node (ref "U4") (pin "30") (pinfunction "PULS0/AD4_30") (pintype "input"))
    )
    (net (code "67") (name "Net-(U4D-PULS1{slash}AD5)") (class "Default")
      (node (ref "R18") (pin "1") (pinfunction "1_1") (pintype "passive"))
      (node (ref "U4") (pin "31") (pinfunction "PULS1/AD5_31") (pintype "input"))
    )
    (net (code "68") (name "Net-(U4D-PULS2{slash}AD6)") (class "Default")
      (node (ref "R17") (pin "1") (pinfunction "1_1") (pintype "passive"))
      (node (ref "U4") (pin "32") (pinfunction "PULS2/AD6_32") (pintype "input"))
    )
    (net (code "69") (name "Net-(U4D-PULS3{slash}AD7)") (class "Default")
      (node (ref "R16") (pin "1") (pinfunction "1_1") (pintype "passive"))
      (node (ref "U4") (pin "33") (pinfunction "PULS3/AD7_33") (pintype "input"))
    )
    (net (code "70") (name "Net-(U4D-RPD{slash}AD2)") (class "Default")
      (node (ref "R21") (pin "1") (pinfunction "1_1") (pintype "passive"))
      (node (ref "U4") (pin "28") (pinfunction "RPD/AD2_28") (pintype "input"))
    )
    (net (code "71") (name "Net-(U4D-~{RST})") (class "Default")
      (node (ref "R24") (pin "1") (pinfunction "1_1") (pintype "passive"))
      (node (ref "U4") (pin "12") (pinfunction "~{RST}_12") (pintype "input"))
    )
    (net (code "72") (name "Net-(U4E-REF)") (class "Default")
      (node (ref "R34") (pin "2") (pinfunction "2_2") (pintype "passive"))
      (node (ref "U4") (pin "43") (pinfunction "REF_43") (pintype "input"))
    )
    (net (code "73") (name "Net-(U4E-VDDA)") (class "Default")
      (node (ref "C23") (pin "1") (pinfunction "1_1") (pintype "passive"))
      (node (ref "C25") (pin "2") (pinfunction "2_2") (pintype "passive"))
      (node (ref "L2") (pin "1") (pinfunction "1_1") (pintype "passive"))
      (node (ref "U4") (pin "42") (pinfunction "VDDA_42") (pintype "power_in"))
    )
    (net (code "74") (name "Net-(U5D-EQ{slash}AD3)") (class "Default")
      (node (ref "R29") (pin "1") (pinfunction "1_1") (pintype "passive"))
      (node (ref "U5") (pin "29") (pinfunction "EQ/AD3_29") (pintype "input"))
    )
    (net (code "75") (name "Net-(U5D-PATT0{slash}AD0)") (class "Default")
      (node (ref "R32") (pin "1") (pinfunction "1_1") (pintype "passive"))
      (node (ref "U5") (pin "26") (pinfunction "PATT0/AD0_26") (pintype "input"))
    )
    (net (code "76") (name "Net-(U5D-PATT1{slash}AD1)") (class "Default")
      (node (ref "R31") (pin "1") (pinfunction "1_1") (pintype "passive"))
      (node (ref "U5") (pin "27") (pinfunction "PATT1/AD1_27") (pintype "input"))
    )
    (net (code "77") (name "Net-(U5D-PULS0{slash}AD4)") (class "Default")
      (node (ref "R28") (pin "1") (pinfunction "1_1") (pintype "passive"))
      (node (ref "U5") (pin "30") (pinfunction "PULS0/AD4_30") (pintype "input"))
    )
    (net (code "78") (name "Net-(U5D-PULS1{slash}AD5)") (class "Default")
      (node (ref "R27") (pin "1") (pinfunction "1_1") (pintype "passive"))
      (node (ref "U5") (pin "31") (pinfunction "PULS1/AD5_31") (pintype "input"))
    )
    (net (code "79") (name "Net-(U5D-PULS2{slash}AD6)") (class "Default")
      (node (ref "R26") (pin "1") (pinfunction "1_1") (pintype "passive"))
      (node (ref "U5") (pin "32") (pinfunction "PULS2/AD6_32") (pintype "input"))
    )
    (net (code "80") (name "Net-(U5D-PULS3{slash}AD7)") (class "Default")
      (node (ref "R25") (pin "1") (pinfunction "1_1") (pintype "passive"))
      (node (ref "U5") (pin "33") (pinfunction "PULS3/AD7_33") (pintype "input"))
    )
    (net (code "81") (name "Net-(U5D-RPD{slash}AD2)") (class "Default")
      (node (ref "R30") (pin "1") (pinfunction "1_1") (pintype "passive"))
      (node (ref "U5") (pin "28") (pinfunction "RPD/AD2_28") (pintype "input"))
    )
    (net (code "82") (name "Net-(U5D-~{RST})") (class "Default")
      (node (ref "R33") (pin "1") (pinfunction "1_1") (pintype "passive"))
      (node (ref "U5") (pin "12") (pinfunction "~{RST}_12") (pintype "input"))
    )
    (net (code "83") (name "Net-(U5E-REF)") (class "Default")
      (node (ref "R35") (pin "2") (pinfunction "2_2") (pintype "passive"))
      (node (ref "U5") (pin "43") (pinfunction "REF_43") (pintype "input"))
    )
    (net (code "84") (name "Net-(U5E-VDDA)") (class "Default")
      (node (ref "C24") (pin "1") (pinfunction "1_1") (pintype "passive"))
      (node (ref "C26") (pin "2") (pinfunction "2_2") (pintype "passive"))
      (node (ref "L3") (pin "1") (pinfunction "1_1") (pintype "passive"))
      (node (ref "U5") (pin "42") (pinfunction "VDDA_42") (pintype "power_in"))
    )
    (net (code "85") (name "Net-(U6-E{slash}D)") (class "Default")
      (node (ref "R45") (pin "1") (pinfunction "1_1") (pintype "passive"))
      (node (ref "U6") (pin "P$1") (pinfunction "E/D_P$1") (pintype "input"))
    )
    (net (code "86") (name "Net-(U7-E{slash}D)") (class "Default")
      (node (ref "R46") (pin "2") (pinfunction "2_2") (pintype "passive"))
      (node (ref "U7") (pin "P$1") (pinfunction "E/D_P$1") (pintype "input"))
    )
    (net (code "87") (name "Net-(X1B-S1)") (class "Default")
      (node (ref "C14") (pin "1") (pinfunction "1_1") (pintype "passive"))
      (node (ref "R12") (pin "2") (pinfunction "2_2") (pintype "passive"))
      (node (ref "X1") (pin "M1") (pinfunction "S1_M1") (pintype "passive"))
      (node (ref "X1") (pin "M4") (pinfunction "S4_M4") (pintype "passive"))
    )
    (net (code "88") (name "Net-(X1B-S2)") (class "Default")
      (node (ref "X1") (pin "M2") (pinfunction "S2_M2") (pintype "passive"))
      (node (ref "X1") (pin "M3") (pinfunction "S3_M3") (pintype "passive"))
    )
    (net (code "89") (name "TCLK") (class "Default")
      (node (ref "R44") (pin "1") (pinfunction "1_1") (pintype "passive"))
      (node (ref "U4") (pin "1") (pinfunction "TCLK_1") (pintype "input"))
      (node (ref "U5") (pin "1") (pinfunction "TCLK_1") (pintype "input"))
    )
    (net (code "90") (name "USB_D_N") (class "Default")
      (node (ref "R6") (pin "1") (pinfunction "1_1") (pintype "passive"))
      (node (ref "U1") (pin "9") (pinfunction "IOB_16A_9") (pintype "bidirectional"))
    )
    (net (code "91") (name "USB_D_P") (class "Default")
      (node (ref "R7") (pin "1") (pinfunction "1_1") (pintype "passive"))
      (node (ref "U1") (pin "10") (pinfunction "IOB_18A_10") (pintype "bidirectional"))
    )
    (net (code "92") (name "USB_PU") (class "Default")
      (node (ref "R9") (pin "1") (pinfunction "1_1") (pintype "passive"))
      (node (ref "U1") (pin "6") (pinfunction "IOB_13B_6") (pintype "bidirectional"))
    )
    (net (code "93") (name "VBUS") (class "Default")
      (node (ref "C12") (pin "1") (pinfunction "1_1") (pintype "passive"))
      (node (ref "C13") (pin "1") (pinfunction "1_1") (pintype "passive"))
      (node (ref "C9") (pin "1") (pinfunction "1_1") (pintype "passive"))
      (node (ref "IC1") (pin "3") (pinfunction "VIN_3") (pintype "power_in"))
      (node (ref "IC3") (pin "1") (pinfunction "IN_1") (pintype "power_in"))
      (node (ref "U2") (pin "5") (pinfunction "VCC_5") (pintype "passive"))
      (node (ref "X1") (pin "1") (pinfunction "1_1") (pintype "input"))
    )
    (net (code "94") (name "VCC_1V2") (class "Default")
      (node (ref "C10") (pin "1") (pinfunction "1_1") (pintype "passive"))
      (node (ref "C5") (pin "2") (pinfunction "2_2") (pintype "passive"))
      (node (ref "C6") (pin "2") (pinfunction "2_2") (pintype "passive"))
      (node (ref "IC1") (pin "2") (pinfunction "VO_2") (pintype "power_in"))
      (node (ref "IC3") (pin "3") (pinfunction "EN_3") (pintype "input"))
      (node (ref "R1") (pin "2") (pinfunction "2_2") (pintype "passive"))
      (node (ref "U1") (pin "30") (pinfunction "VCC_30") (pintype "power_in"))
      (node (ref "U1") (pin "5") (pinfunction "VCC_5") (pintype "power_in"))
    )
    (net (code "95") (name "VCC_3V3") (class "Default")
      (node (ref "C1") (pin "2") (pinfunction "2_2") (pintype "passive"))
      (node (ref "C11") (pin "1") (pinfunction "1_1") (pintype "passive"))
      (node (ref "C15") (pin "1") (pinfunction "1_1") (pintype "passive"))
      (node (ref "C16") (pin "1") (pinfunction "1_1") (pintype "passive"))
      (node (ref "C17") (pin "1") (pinfunction "1_1") (pintype "passive"))
      (node (ref "C18") (pin "1") (pinfunction "1_1") (pintype "passive"))
      (node (ref "C19") (pin "1") (pinfunction "1_1") (pintype "passive"))
      (node (ref "C2") (pin "2") (pinfunction "2_2") (pintype "passive"))
      (node (ref "C20") (pin "1") (pinfunction "1_1") (pintype "passive"))
      (node (ref "C21") (pin "1") (pinfunction "1_1") (pintype "passive"))
      (node (ref "C22") (pin "1") (pinfunction "1_1") (pintype "passive"))
      (node (ref "C27") (pin "2") (pinfunction "2_2") (pintype "passive"))
      (node (ref "C28") (pin "2") (pinfunction "2_2") (pintype "passive"))
      (node (ref "C29") (pin "2") (pinfunction "2_2") (pintype "passive"))
      (node (ref "C3") (pin "2") (pinfunction "2_2") (pintype "passive"))
      (node (ref "C30") (pin "2") (pinfunction "2_2") (pintype "passive"))
      (node (ref "C4") (pin "2") (pinfunction "2_2") (pintype "passive"))
      (node (ref "D1") (pin "1") (pinfunction "C_1") (pintype "passive"))
      (node (ref "D2") (pin "1") (pinfunction "C_1") (pintype "passive"))
      (node (ref "D3") (pin "1") (pinfunction "C_1") (pintype "passive"))
      (node (ref "D4") (pin "1") (pinfunction "C_1") (pintype "passive"))
      (node (ref "IC2") (pin "3") (pinfunction "~{WP(D2})_3") (pintype "bidirectional"))
      (node (ref "IC2") (pin "7") (pinfunction "~{HOLD(D3})_7") (pintype "bidirectional"))
      (node (ref "IC2") (pin "8") (pinfunction "VCC_8") (pintype "power_in"))
      (node (ref "IC3") (pin "5") (pinfunction "OUT_5") (pintype "power_in"))
      (node (ref "IC4") (pin "4") (pinfunction "VCC_4") (pintype "passive"))
      (node (ref "JP1") (pin "1") (pinfunction "1_1") (pintype "passive"))
      (node (ref "L2") (pin "2") (pinfunction "2_2") (pintype "passive"))
      (node (ref "L3") (pin "2") (pinfunction "2_2") (pintype "passive"))
      (node (ref "LED1") (pin "2") (pinfunction "ANODE_2") (pintype "power_in"))
      (node (ref "LOS1") (pin "A") (pinfunction "A_A") (pintype "passive"))
      (node (ref "LOS2") (pin "A") (pinfunction "A_A") (pintype "passive"))
      (node (ref "PWR") (pin "A") (pinfunction "A_A") (pintype "passive"))
      (node (ref "R10") (pin "2") (pinfunction "2_2") (pintype "passive"))
      (node (ref "R13") (pin "2") (pinfunction "2_2") (pintype "passive"))
      (node (ref "R14") (pin "1") (pinfunction "1_1") (pintype "passive"))
      (node (ref "R24") (pin "2") (pinfunction "2_2") (pintype "passive"))
      (node (ref "R33") (pin "2") (pinfunction "2_2") (pintype "passive"))
      (node (ref "R8") (pin "2") (pinfunction "2_2") (pintype "passive"))
      (node (ref "U1") (pin "1") (pinfunction "VCC_IO_2_1") (pintype "power_in"))
      (node (ref "U1") (pin "22") (pinfunction "VCC_IO_1_22") (pintype "power_in"))
      (node (ref "U1") (pin "24") (pinfunction "VPP_2V5_24") (pintype "power_in"))
      (node (ref "U1") (pin "33") (pinfunction "VCC_IO_0_33") (pintype "power_in"))
      (node (ref "U3") (pin "5") (pinfunction "VCC_5") (pintype "passive"))
      (node (ref "U4") (pin "16") (pinfunction "MODE0_16") (pintype "input"))
      (node (ref "U4") (pin "19") (pinfunction "VDDIO_19") (pintype "power_in"))
      (node (ref "U4") (pin "35") (pinfunction "VDDT_35") (pintype "power_in"))
      (node (ref "U4") (pin "8") (pinfunction "VDDD_8") (pintype "power_in"))
      (node (ref "U5") (pin "16") (pinfunction "MODE0_16") (pintype "input"))
      (node (ref "U5") (pin "19") (pinfunction "VDDIO_19") (pintype "power_in"))
      (node (ref "U5") (pin "35") (pinfunction "VDDT_35") (pintype "power_in"))
      (node (ref "U5") (pin "8") (pinfunction "VDDD_8") (pintype "power_in"))
      (node (ref "U6") (pin "P$4") (pinfunction "VCC_P$4") (pintype "power_in"))
      (node (ref "U7") (pin "P$4") (pinfunction "VCC_P$4") (pintype "power_in"))
    )
    (net (code "96") (name "unconnected-(TR1A-P$2-Pad15)") (class "Default")
      (node (ref "TR1") (pin "15") (pinfunction "P$2_15") (pintype "bidirectional"))
    )
    (net (code "97") (name "unconnected-(TR1A-P$5-Pad2)") (class "Default")
      (node (ref "TR1") (pin "2") (pinfunction "P$5_2") (pintype "bidirectional"))
    )
    (net (code "98") (name "unconnected-(TR2A-P$2-Pad15)") (class "Default")
      (node (ref "TR2") (pin "15") (pinfunction "P$2_15") (pintype "bidirectional"))
    )
    (net (code "99") (name "unconnected-(TR2A-P$5-Pad2)") (class "Default")
      (node (ref "TR2") (pin "2") (pinfunction "P$5_2") (pintype "bidirectional"))
    )
    (net (code "100") (name "unconnected-(U1-IOB_4A-Pad48)") (class "Default")
      (node (ref "U1") (pin "48") (pinfunction "IOB_4A_48") (pintype "bidirectional"))
    )
    (net (code "101") (name "unconnected-(U1-IOB_6A-Pad2)") (class "Default")
      (node (ref "U1") (pin "2") (pinfunction "IOB_6A_2") (pintype "bidirectional"))
    )
    (net (code "102") (name "unconnected-(U1-IOB_8A-Pad4)") (class "Default")
      (node (ref "U1") (pin "4") (pinfunction "IOB_8A_4") (pintype "bidirectional"))
    )
    (net (code "103") (name "unconnected-(U1-IOB_9B-Pad3)") (class "Default")
      (node (ref "U1") (pin "3") (pinfunction "IOB_9B_3") (pintype "bidirectional"))
    )
    (net (code "104") (name "unconnected-(U1-IOB_20A-Pad11)") (class "Default")
      (node (ref "U1") (pin "11") (pinfunction "IOB_20A_11") (pintype "bidirectional"))
    )
    (net (code "105") (name "unconnected-(U1-IOB_22A-Pad12)") (class "Default")
      (node (ref "U1") (pin "12") (pinfunction "IOB_22A_12") (pintype "bidirectional"))
    )
    (net (code "106") (name "unconnected-(U1-IOB_23B-Pad21)") (class "Default")
      (node (ref "U1") (pin "21") (pinfunction "IOB_23B_21") (pintype "bidirectional"))
    )
    (net (code "107") (name "unconnected-(U1-IOB_24A-Pad13)") (class "Default")
      (node (ref "U1") (pin "13") (pinfunction "IOB_24A_13") (pintype "bidirectional"))
    )
    (net (code "108") (name "unconnected-(U1-IOB_29B-Pad19)") (class "Default")
      (node (ref "U1") (pin "19") (pinfunction "IOB_29B_19") (pintype "bidirectional"))
    )
    (net (code "109") (name "unconnected-(U1-IOB_31B-Pad18)") (class "Default")
      (node (ref "U1") (pin "18") (pinfunction "IOB_31B_18") (pintype "bidirectional"))
    )
    (net (code "110") (name "unconnected-(U1-IOT_37A-Pad23)") (class "Default")
      (node (ref "U1") (pin "23") (pinfunction "IOT_37A_23") (pintype "bidirectional"))
    )
    (net (code "111") (name "unconnected-(U1-IOT_38B-Pad27)") (class "Default")
      (node (ref "U1") (pin "27") (pinfunction "IOT_38B_27") (pintype "bidirectional"))
    )
    (net (code "112") (name "unconnected-(U1-IOT_39A-Pad26)") (class "Default")
      (node (ref "U1") (pin "26") (pinfunction "IOT_39A_26") (pintype "bidirectional"))
    )
    (net (code "113") (name "unconnected-(U1-IOT_41A-Pad28)") (class "Default")
      (node (ref "U1") (pin "28") (pinfunction "IOT_41A_28") (pintype "bidirectional"))
    )
    (net (code "114") (name "unconnected-(U1-IOT_45A_G1-Pad37)") (class "Default")
      (node (ref "U1") (pin "37") (pinfunction "IOT_45A_G1_37") (pintype "bidirectional"))
    )
    (net (code "115") (name "unconnected-(U1-IOT_46B_G0-Pad35)") (class "Default")
      (node (ref "U1") (pin "35") (pinfunction "IOT_46B_G0_35") (pintype "bidirectional"))
    )
    (net (code "116") (name "unconnected-(U1-IOT_48B-Pad36)") (class "Default")
      (node (ref "U1") (pin "36") (pinfunction "IOT_48B_36") (pintype "bidirectional"))
    )
    (net (code "117") (name "unconnected-(U3-2A-Pad6)") (class "Default")
      (node (ref "U3") (pin "6") (pinfunction "2A_6") (pintype "passive"))
    )
    (net (code "118") (name "unconnected-(U3-2B-Pad4)") (class "Default")
      (node (ref "U3") (pin "4") (pinfunction "2B_4") (pintype "passive"))
    )
    (net (code "119") (name "unconnected-(U4A-CV{slash}RDN-Pad6)") (class "Default")
      (node (ref "U4") (pin "6") (pinfunction "CV/RDN_6") (pintype "output"))
    )
    (net (code "120") (name "unconnected-(U4A-TDN-Pad3)") (class "Default")
      (node (ref "U4") (pin "3") (pinfunction "TDN_3") (pintype "input"))
    )
    (net (code "121") (name "unconnected-(U4A-TD{slash}TDP-Pad2)") (class "Default")
      (node (ref "U4") (pin "2") (pinfunction "TD/TDP_2") (pintype "input"))
    )
    (net (code "122") (name "unconnected-(U4B-TRING-Pad36)") (class "Default")
      (node (ref "U4") (pin "36") (pinfunction "TRING_36") (pintype "output"))
    )
    (net (code "123") (name "unconnected-(U4B-TTIP-Pad37)") (class "Default")
      (node (ref "U4") (pin "37") (pinfunction "TTIP_37") (pintype "output"))
    )
    (net (code "124") (name "unconnected-(U4C-~{INT}-Pad20)") (class "Default")
      (node (ref "U4") (pin "20") (pinfunction "~{INT}_20") (pintype "output"))
    )
    (net (code "125") (name "unconnected-(U4F-IC0-Pad44)") (class "Default")
      (node (ref "U4") (pin "44") (pinfunction "IC0_44") (pintype "no_connect"))
    )
    (net (code "126") (name "unconnected-(U4F-IC1-Pad34)") (class "Default")
      (node (ref "U4") (pin "34") (pinfunction "IC1_34") (pintype "no_connect"))
    )
    (net (code "127") (name "unconnected-(U5A-CV{slash}RDN-Pad6)") (class "Default")
      (node (ref "U5") (pin "6") (pinfunction "CV/RDN_6") (pintype "output"))
    )
    (net (code "128") (name "unconnected-(U5A-TDN-Pad3)") (class "Default")
      (node (ref "U5") (pin "3") (pinfunction "TDN_3") (pintype "input"))
    )
    (net (code "129") (name "unconnected-(U5A-TD{slash}TDP-Pad2)") (class "Default")
      (node (ref "U5") (pin "2") (pinfunction "TD/TDP_2") (pintype "input"))
    )
    (net (code "130") (name "unconnected-(U5B-TRING-Pad36)") (class "Default")
      (node (ref "U5") (pin "36") (pinfunction "TRING_36") (pintype "output"))
    )
    (net (code "131") (name "unconnected-(U5B-TTIP-Pad37)") (class "Default")
      (node (ref "U5") (pin "37") (pinfunction "TTIP_37") (pintype "output"))
    )
    (net (code "132") (name "unconnected-(U5C-~{INT}-Pad20)") (class "Default")
      (node (ref "U5") (pin "20") (pinfunction "~{INT}_20") (pintype "output"))
    )
    (net (code "133") (name "unconnected-(U5F-IC0-Pad44)") (class "Default")
      (node (ref "U5") (pin "44") (pinfunction "IC0_44") (pintype "no_connect"))
    )
    (net (code "134") (name "unconnected-(U5F-IC1-Pad34)") (class "Default")
      (node (ref "U5") (pin "34") (pinfunction "IC1_34") (pintype "no_connect"))
    )
    (net (code "135") (name "unconnected-(X1-Pad4)") (class "Default")
      (node (ref "X1") (pin "4") (pinfunction "4_4") (pintype "input"))
    )
    (net (code "136") (name "unconnected-(X2-TIP-Pad2)") (class "Default")
      (node (ref "X2") (pin "2") (pinfunction "TIP_2") (pintype "passive"))
    )
    (net (code "137") (name "~{CRESET}") (class "Default")
      (node (ref "JP1") (pin "7") (pinfunction "7_7") (pintype "passive"))
      (node (ref "U1") (pin "8") (pinfunction "~{CRESET_B}_8") (pintype "bidirectional"))
    )
  )
)
